# galvanika-board-2_2.net
KiCad netlist of a schematic drawn in EAGLE
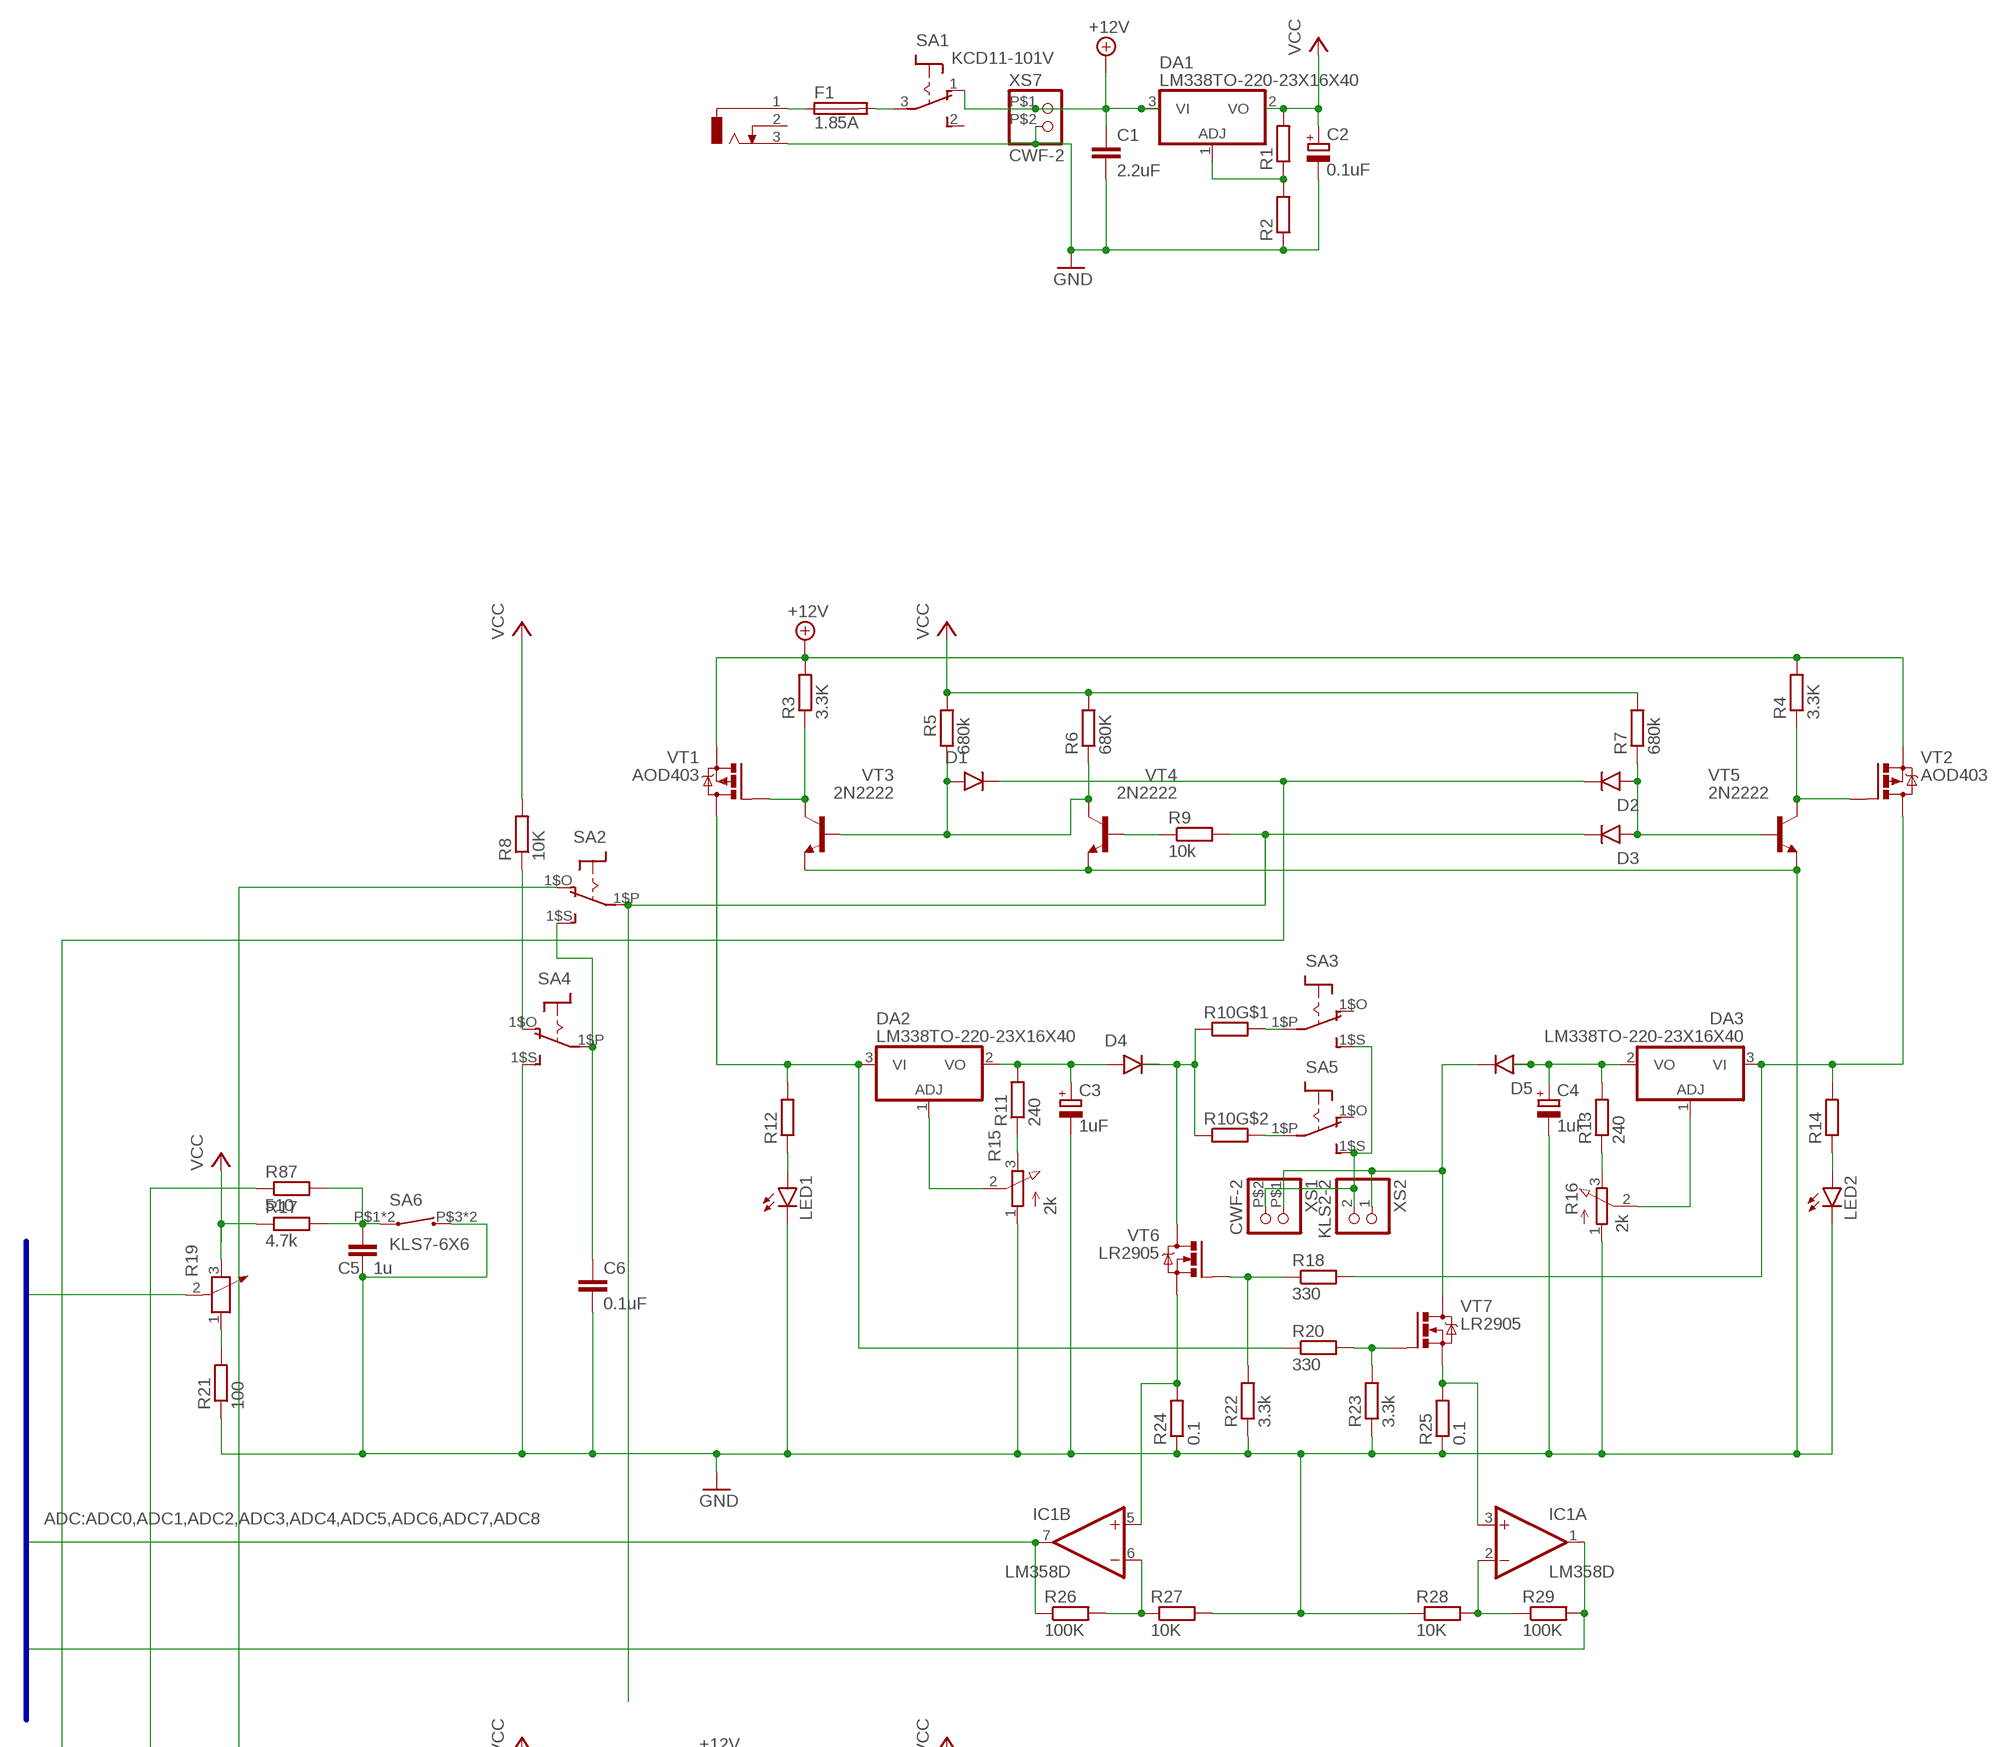
[diagram p0: schematic, sheet 1, part 1 of 2]
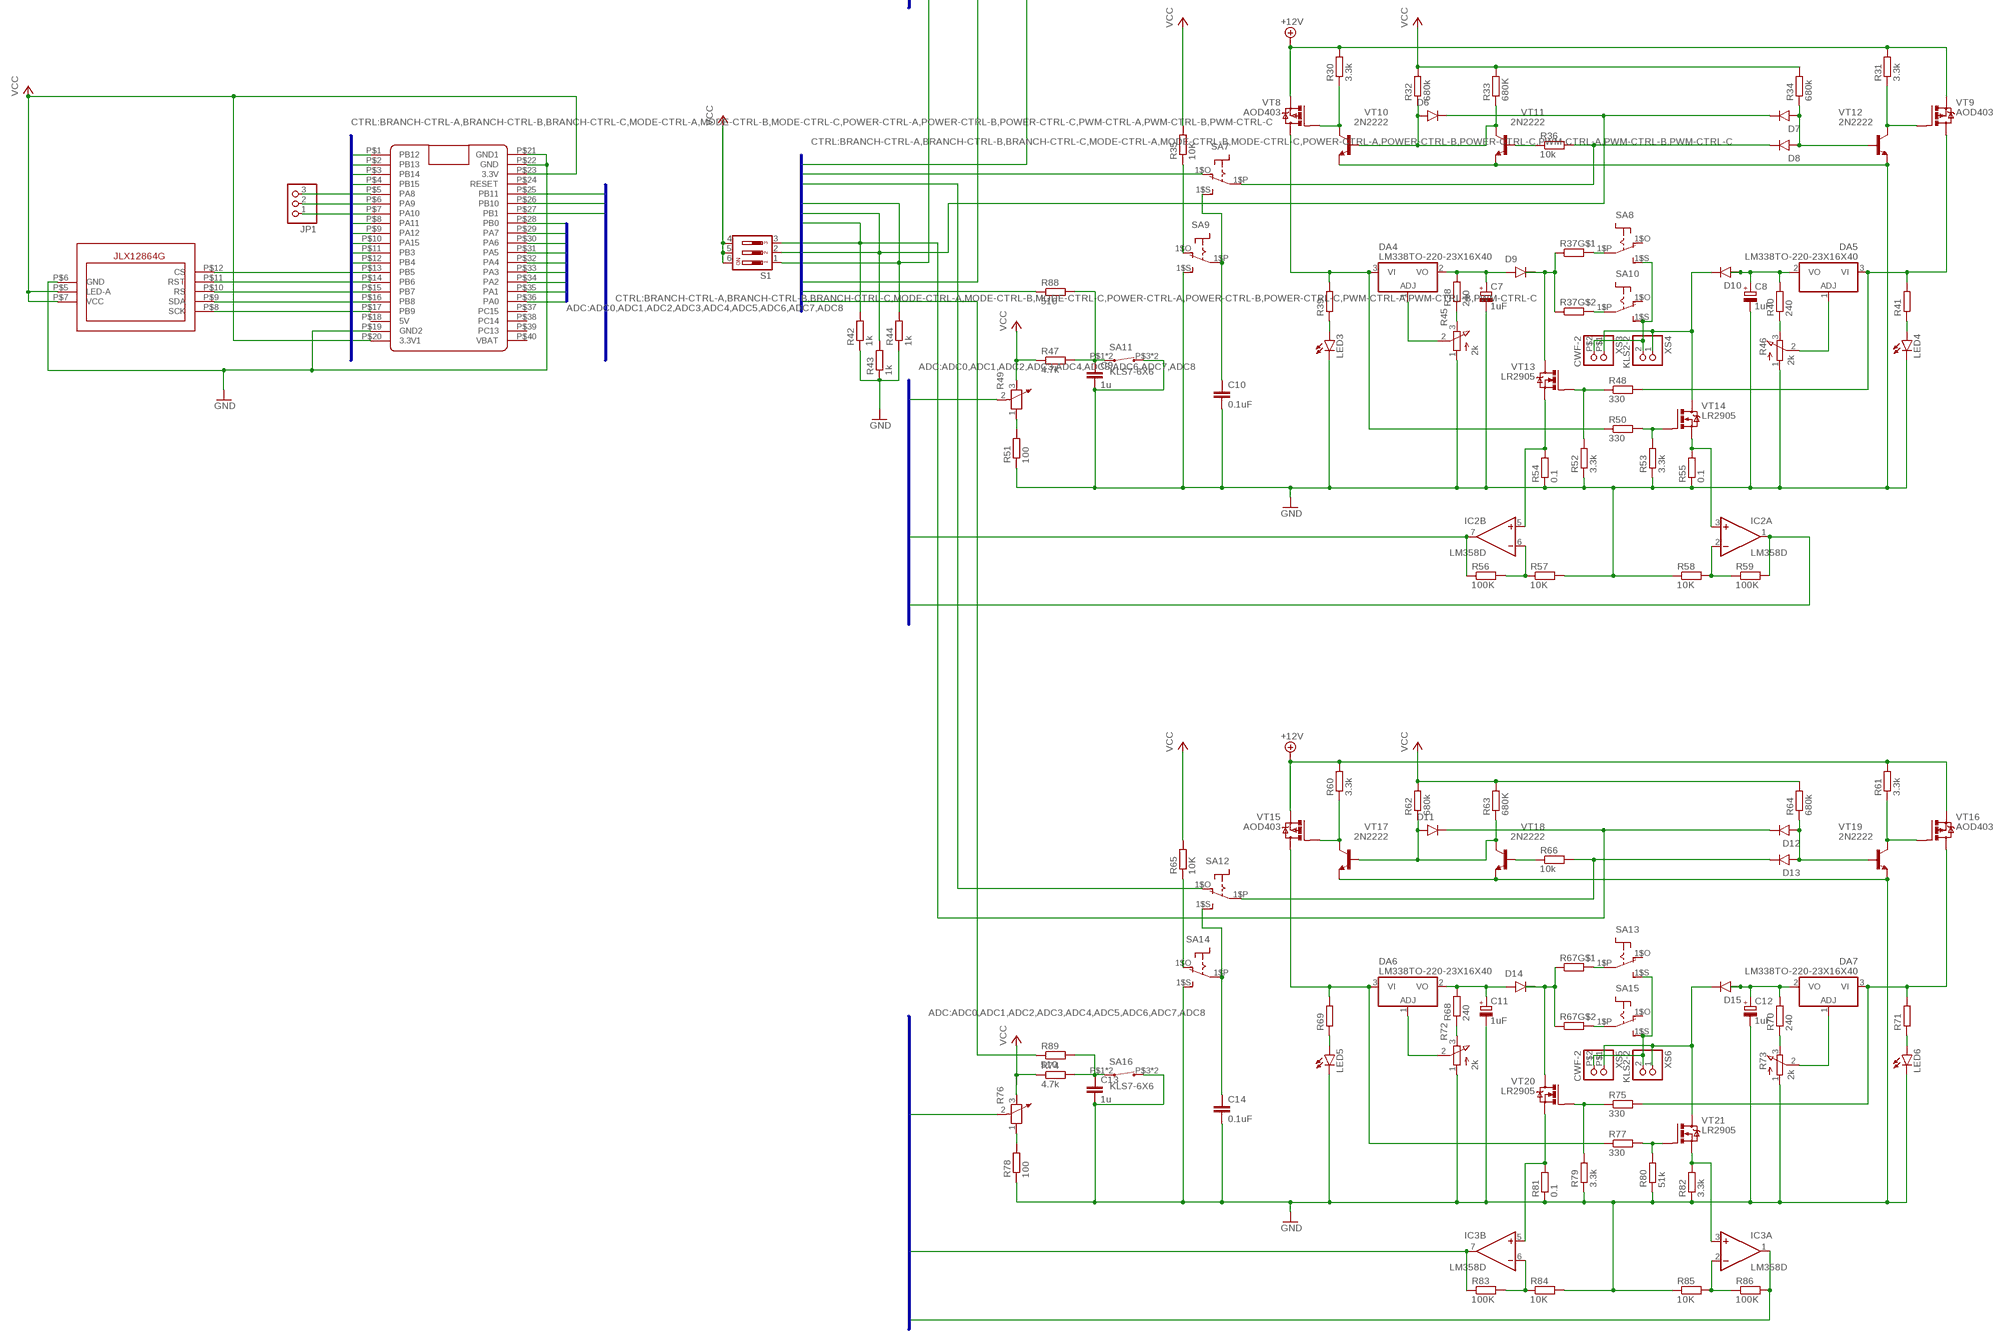
[diagram p1: schematic, sheet 1, part 2 of 2]

(export (version "E")
  (design (tool "Eeschema 10.0.6"))
  (components
    (comp (ref "C1")
      (value "2.2uF")
      (footprint "eagle-import:C025-025X050")
      (libsource (lib "eagle-import") (part "C-EU025-025X050"))
    )
    (comp (ref "C2")
      (value "0.1uF")
      (footprint "eagle-import:E2,5-5")
      (libsource (lib "eagle-import") (part "rcl_334_CPOL-EUE2.5-5"))
    )
    (comp (ref "C3")
      (value "1uF")
      (footprint "eagle-import:E5-4")
      (libsource (lib "eagle-import") (part "CPOL-EUE5-4"))
    )
    (comp (ref "C4")
      (value "1uF")
      (footprint "eagle-import:E5-4")
      (libsource (lib "eagle-import") (part "CPOL-EUE5-4"))
    )
    (comp (ref "C5")
      (value "1u")
      (footprint "eagle-import:C1206")
      (libsource (lib "eagle-import") (part "C-EUC1206"))
    )
    (comp (ref "C6")
      (value "0.1uF")
      (footprint "eagle-import:C1206")
      (libsource (lib "eagle-import") (part "C-EUC1206"))
    )
    (comp (ref "C7")
      (value "1uF")
      (footprint "eagle-import:E5-4")
      (libsource (lib "eagle-import") (part "CPOL-EUE5-4"))
    )
    (comp (ref "C8")
      (value "1uF")
      (footprint "eagle-import:E5-4")
      (libsource (lib "eagle-import") (part "CPOL-EUE5-4"))
    )
    (comp (ref "C9")
      (value "1u")
      (footprint "eagle-import:C1206")
      (libsource (lib "eagle-import") (part "C-EUC1206"))
    )
    (comp (ref "C10")
      (value "0.1uF")
      (footprint "eagle-import:C1206")
      (libsource (lib "eagle-import") (part "C-EUC1206"))
    )
    (comp (ref "C11")
      (value "1uF")
      (footprint "eagle-import:E5-4")
      (libsource (lib "eagle-import") (part "CPOL-EUE5-4"))
    )
    (comp (ref "C12")
      (value "1uF")
      (footprint "eagle-import:E5-4")
      (libsource (lib "eagle-import") (part "CPOL-EUE5-4"))
    )
    (comp (ref "C13")
      (value "1u")
      (footprint "eagle-import:C1206")
      (libsource (lib "eagle-import") (part "C-EUC1206"))
    )
    (comp (ref "C14")
      (value "0.1uF")
      (footprint "eagle-import:C1206")
      (libsource (lib "eagle-import") (part "C-EUC1206"))
    )
    (comp (ref "D1")
      (value "1N4001")
      (footprint "eagle-import:DO41-10")
      (libsource (lib "eagle-import") (part "1N4001"))
    )
    (comp (ref "D2")
      (value "1N4001")
      (footprint "eagle-import:DO41-10")
      (libsource (lib "eagle-import") (part "1N4001"))
    )
    (comp (ref "D3")
      (value "1N4001")
      (footprint "eagle-import:DO41-10")
      (libsource (lib "eagle-import") (part "1N4001"))
    )
    (comp (ref "D4")
      (value "1N4001")
      (footprint "eagle-import:DO41-10")
      (libsource (lib "eagle-import") (part "1N4001"))
    )
    (comp (ref "D5")
      (value "1N4001")
      (footprint "eagle-import:DO41-10")
      (libsource (lib "eagle-import") (part "1N4001"))
    )
    (comp (ref "D6")
      (value "1N4001")
      (footprint "eagle-import:DO41-10")
      (libsource (lib "eagle-import") (part "1N4001"))
    )
    (comp (ref "D7")
      (value "1N4001")
      (footprint "eagle-import:DO41-10")
      (libsource (lib "eagle-import") (part "1N4001"))
    )
    (comp (ref "D8")
      (value "1N4001")
      (footprint "eagle-import:DO41-10")
      (libsource (lib "eagle-import") (part "1N4001"))
    )
    (comp (ref "D9")
      (value "1N4001")
      (footprint "eagle-import:DO41-10")
      (libsource (lib "eagle-import") (part "1N4001"))
    )
    (comp (ref "D10")
      (value "1N4001")
      (footprint "eagle-import:DO41-10")
      (libsource (lib "eagle-import") (part "1N4001"))
    )
    (comp (ref "D11")
      (value "1N4001")
      (footprint "eagle-import:DO41-10")
      (libsource (lib "eagle-import") (part "1N4001"))
    )
    (comp (ref "D12")
      (value "1N4001")
      (footprint "eagle-import:DO41-10")
      (libsource (lib "eagle-import") (part "1N4001"))
    )
    (comp (ref "D13")
      (value "1N4001")
      (footprint "eagle-import:DO41-10")
      (libsource (lib "eagle-import") (part "1N4001"))
    )
    (comp (ref "D14")
      (value "1N4001")
      (footprint "eagle-import:DO41-10")
      (libsource (lib "eagle-import") (part "1N4001"))
    )
    (comp (ref "D15")
      (value "1N4001")
      (footprint "eagle-import:DO41-10")
      (libsource (lib "eagle-import") (part "1N4001"))
    )
    (comp (ref "DA1")
      (value "LM338TO-220-23X16X40")
      (footprint "eagle-import:TO220-23X16X40")
      (libsource (lib "eagle-import") (part "LM338TO-220-23X16X40"))
    )
    (comp (ref "DA2")
      (value "LM338TO-220-23X16X40")
      (footprint "eagle-import:TO220-23X16X40")
      (libsource (lib "eagle-import") (part "LM338TO-220-23X16X40"))
    )
    (comp (ref "DA3")
      (value "LM338TO-220-23X16X40")
      (footprint "eagle-import:TO220-23X16X40")
      (libsource (lib "eagle-import") (part "LM338TO-220-23X16X40"))
    )
    (comp (ref "DA4")
      (value "LM338TO-220-23X16X40")
      (footprint "eagle-import:TO220-23X16X40")
      (libsource (lib "eagle-import") (part "LM338TO-220-23X16X40"))
    )
    (comp (ref "DA5")
      (value "LM338TO-220-23X16X40")
      (footprint "eagle-import:TO220-23X16X40")
      (libsource (lib "eagle-import") (part "LM338TO-220-23X16X40"))
    )
    (comp (ref "DA6")
      (value "LM338TO-220-23X16X40")
      (footprint "eagle-import:TO220-23X16X40")
      (libsource (lib "eagle-import") (part "LM338TO-220-23X16X40"))
    )
    (comp (ref "DA7")
      (value "LM338TO-220-23X16X40")
      (footprint "eagle-import:TO220-23X16X40")
      (libsource (lib "eagle-import") (part "LM338TO-220-23X16X40"))
    )
    (comp (ref "DD1")
      (value "BLUE_PILL")
      (footprint "eagle-import:BLUE_PILL")
      (libsource (lib "eagle-import") (part "BLUE_PILL"))
    )
    (comp (ref "F1")
      (value "1.85A")
      (footprint "eagle-import:MF-R")
      (libsource (lib "eagle-import") (part "MF-R"))
    )
    (comp (ref "HG1")
      (value "JLX12864G")
      (footprint "eagle-import:JLX12864G")
      (libsource (lib "eagle-import") (part "JLX12864G"))
    )
    (comp (ref "IC1")
      (value "LM358D")
      (footprint "eagle-import:SO08")
      (libsource (lib "eagle-import") (part "LM358D"))
    )
    (comp (ref "IC2")
      (value "LM358D")
      (footprint "eagle-import:SO08")
      (libsource (lib "eagle-import") (part "LM358D"))
    )
    (comp (ref "IC3")
      (value "LM358D")
      (footprint "eagle-import:SO08")
      (libsource (lib "eagle-import") (part "LM358D"))
    )
    (comp (ref "J1")
      (value "DCJ0303")
      (footprint "eagle-import:DCJ0303")
      (libsource (lib "eagle-import") (part "DCJ0303"))
    )
    (comp (ref "JP1")
      (value "PINHD-1X3")
      (footprint "eagle-import:1X03")
      (libsource (lib "eagle-import") (part "PINHD-1X3"))
    )
    (comp (ref "LED1")
      (value "LED3MM")
      (footprint "eagle-import:LED3MM")
      (libsource (lib "eagle-import") (part "LED3MM"))
    )
    (comp (ref "LED2")
      (value "LED3MM")
      (footprint "eagle-import:LED3MM")
      (libsource (lib "eagle-import") (part "LED3MM"))
    )
    (comp (ref "LED3")
      (value "LED3MM")
      (footprint "eagle-import:LED3MM")
      (libsource (lib "eagle-import") (part "LED3MM"))
    )
    (comp (ref "LED4")
      (value "LED3MM")
      (footprint "eagle-import:LED3MM")
      (libsource (lib "eagle-import") (part "LED3MM"))
    )
    (comp (ref "LED5")
      (value "LED3MM")
      (footprint "eagle-import:LED3MM")
      (libsource (lib "eagle-import") (part "LED3MM"))
    )
    (comp (ref "LED6")
      (value "LED3MM")
      (footprint "eagle-import:LED3MM")
      (libsource (lib "eagle-import") (part "LED3MM"))
    )
    (comp (ref "R1")
      (value "R-EU_0207/10")
      (footprint "eagle-import:0207_10")
      (libsource (lib "eagle-import") (part "R-EU_0207/10"))
    )
    (comp (ref "R2")
      (value "R-EU_0207/10")
      (footprint "eagle-import:0207_10")
      (libsource (lib "eagle-import") (part "R-EU_0207/10"))
    )
    (comp (ref "R3")
      (value "3.3K")
      (footprint "eagle-import:0207_10")
      (libsource (lib "eagle-import") (part "rcl_334_R-EU_0207/10"))
    )
    (comp (ref "R4")
      (value "3.3K")
      (footprint "eagle-import:0207_10")
      (libsource (lib "eagle-import") (part "rcl_334_R-EU_0207/10"))
    )
    (comp (ref "R5")
      (value "680k")
      (footprint "eagle-import:0207_10")
      (libsource (lib "eagle-import") (part "rcl_334_R-EU_0207/10"))
    )
    (comp (ref "R6")
      (value "680K")
      (footprint "eagle-import:0207_10")
      (libsource (lib "eagle-import") (part "rcl_334_R-EU_0207/10"))
    )
    (comp (ref "R7")
      (value "680k")
      (footprint "eagle-import:0207_10")
      (libsource (lib "eagle-import") (part "rcl_334_R-EU_0207/10"))
    )
    (comp (ref "R8")
      (value "10K")
      (footprint "eagle-import:0207_10")
      (libsource (lib "eagle-import") (part "rcl_334_R-EU_0207/10"))
    )
    (comp (ref "R9")
      (value "10k")
      (footprint "eagle-import:0207_10")
      (libsource (lib "eagle-import") (part "rcl_334_R-EU_0207/10"))
    )
    (comp (ref "R10")
      (value "SQP-5W-2")
      (footprint "eagle-import:SQP-5W-2")
      (libsource (lib "eagle-import") (part "SQP-5W-2"))
    )
    (comp (ref "R11")
      (value "240")
      (footprint "eagle-import:0207_10")
      (libsource (lib "eagle-import") (part "rcl_334_R-EU_0207/10"))
    )
    (comp (ref "R12")
      (value "R-EU_0207/10")
      (footprint "eagle-import:0207_10")
      (libsource (lib "eagle-import") (part "rcl_334_R-EU_0207/10"))
    )
    (comp (ref "R13")
      (value "240")
      (footprint "eagle-import:0207_10")
      (libsource (lib "eagle-import") (part "rcl_334_R-EU_0207/10"))
    )
    (comp (ref "R14")
      (value "R-EU_0207/10")
      (footprint "eagle-import:0207_10")
      (libsource (lib "eagle-import") (part "rcl_334_R-EU_0207/10"))
    )
    (comp (ref "R15")
      (value "2k")
      (footprint "eagle-import:3RP_1610N")
      (libsource (lib "eagle-import") (part "3RP/1610N"))
    )
    (comp (ref "R16")
      (value "2k")
      (footprint "eagle-import:3RP_1610N")
      (libsource (lib "eagle-import") (part "3RP/1610N"))
    )
    (comp (ref "R17")
      (value "4.7k")
      (footprint "eagle-import:R1206")
      (libsource (lib "eagle-import") (part "R-EU_R1206"))
    )
    (comp (ref "R18")
      (value "330")
      (footprint "eagle-import:0207_10")
      (libsource (lib "eagle-import") (part "rcl_334_R-EU_0207/10"))
    )
    (comp (ref "R19")
      (value "R0904N")
      (footprint "eagle-import:R0904N")
      (libsource (lib "eagle-import") (part "R0904N"))
    )
    (comp (ref "R20")
      (value "330")
      (footprint "eagle-import:0207_10")
      (libsource (lib "eagle-import") (part "rcl_334_R-EU_0207/10"))
    )
    (comp (ref "R21")
      (value "100")
      (footprint "eagle-import:R1206")
      (libsource (lib "eagle-import") (part "R-EU_R1206"))
    )
    (comp (ref "R22")
      (value "3.3k")
      (footprint "eagle-import:0207_10")
      (libsource (lib "eagle-import") (part "rcl_334_R-EU_0207/10"))
    )
    (comp (ref "R23")
      (value "3.3k")
      (footprint "eagle-import:0207_10")
      (libsource (lib "eagle-import") (part "rcl_334_R-EU_0207/10"))
    )
    (comp (ref "R24")
      (value "0.1")
      (footprint "eagle-import:0411_12")
      (libsource (lib "eagle-import") (part "rcl_334_R-EU_0411/12"))
    )
    (comp (ref "R25")
      (value "0.1")
      (footprint "eagle-import:0411_12")
      (libsource (lib "eagle-import") (part "rcl_334_R-EU_0411/12"))
    )
    (comp (ref "R26")
      (value "100K")
      (footprint "eagle-import:R1206")
      (libsource (lib "eagle-import") (part "rcl_334_R-EU_R1206"))
    )
    (comp (ref "R27")
      (value "10K")
      (footprint "eagle-import:R1206")
      (libsource (lib "eagle-import") (part "rcl_334_R-EU_R1206"))
    )
    (comp (ref "R28")
      (value "10K")
      (footprint "eagle-import:R1206")
      (libsource (lib "eagle-import") (part "rcl_334_R-EU_R1206"))
    )
    (comp (ref "R29")
      (value "100K")
      (footprint "eagle-import:R1206")
      (libsource (lib "eagle-import") (part "rcl_334_R-EU_R1206"))
    )
    (comp (ref "R30")
      (value "3.3k")
      (footprint "eagle-import:0207_10")
      (libsource (lib "eagle-import") (part "rcl_334_R-EU_0207/10"))
    )
    (comp (ref "R31")
      (value "3.3k")
      (footprint "eagle-import:0207_10")
      (libsource (lib "eagle-import") (part "rcl_334_R-EU_0207/10"))
    )
    (comp (ref "R32")
      (value "680k")
      (footprint "eagle-import:0207_10")
      (libsource (lib "eagle-import") (part "rcl_334_R-EU_0207/10"))
    )
    (comp (ref "R33")
      (value "680K")
      (footprint "eagle-import:0207_10")
      (libsource (lib "eagle-import") (part "rcl_334_R-EU_0207/10"))
    )
    (comp (ref "R34")
      (value "680k")
      (footprint "eagle-import:0207_10")
      (libsource (lib "eagle-import") (part "rcl_334_R-EU_0207/10"))
    )
    (comp (ref "R35")
      (value "10K")
      (footprint "eagle-import:0207_10")
      (libsource (lib "eagle-import") (part "rcl_334_R-EU_0207/10"))
    )
    (comp (ref "R36")
      (value "10k")
      (footprint "eagle-import:0207_10")
      (libsource (lib "eagle-import") (part "rcl_334_R-EU_0207/10"))
    )
    (comp (ref "R37")
      (value "SQP-5W-2")
      (footprint "eagle-import:SQP-5W-2")
      (libsource (lib "eagle-import") (part "SQP-5W-2"))
    )
    (comp (ref "R38")
      (value "240")
      (footprint "eagle-import:0207_10")
      (libsource (lib "eagle-import") (part "R-EU_0207/10"))
    )
    (comp (ref "R39")
      (value "R-EU_0207/10")
      (footprint "eagle-import:0207_10")
      (libsource (lib "eagle-import") (part "R-EU_0207/10"))
    )
    (comp (ref "R40")
      (value "240")
      (footprint "eagle-import:0207_10")
      (libsource (lib "eagle-import") (part "rcl_334_R-EU_0207/10"))
    )
    (comp (ref "R41")
      (value "R-EU_0207/10")
      (footprint "eagle-import:0207_10")
      (libsource (lib "eagle-import") (part "R-EU_0207/10"))
    )
    (comp (ref "R42")
      (value "1k")
      (footprint "eagle-import:R1206")
      (libsource (lib "eagle-import") (part "R-EU_R1206"))
    )
    (comp (ref "R43")
      (value "1k")
      (footprint "eagle-import:R1206")
      (libsource (lib "eagle-import") (part "R-EU_R1206"))
    )
    (comp (ref "R44")
      (value "1k")
      (footprint "eagle-import:R1206")
      (libsource (lib "eagle-import") (part "R-EU_R1206"))
    )
    (comp (ref "R45")
      (value "2k")
      (footprint "eagle-import:3RP_1610N")
      (libsource (lib "eagle-import") (part "3RP/1610N"))
    )
    (comp (ref "R46")
      (value "2k")
      (footprint "eagle-import:3RP_1610N")
      (libsource (lib "eagle-import") (part "3RP/1610N"))
    )
    (comp (ref "R47")
      (value "4.7k")
      (footprint "eagle-import:R1206")
      (libsource (lib "eagle-import") (part "R-EU_R1206"))
    )
    (comp (ref "R48")
      (value "330")
      (footprint "eagle-import:0207_10")
      (libsource (lib "eagle-import") (part "rcl_334_R-EU_0207/10"))
    )
    (comp (ref "R49")
      (value "R0904N")
      (footprint "eagle-import:R0904N")
      (libsource (lib "eagle-import") (part "R0904N"))
    )
    (comp (ref "R50")
      (value "330")
      (footprint "eagle-import:0207_10")
      (libsource (lib "eagle-import") (part "rcl_334_R-EU_0207/10"))
    )
    (comp (ref "R51")
      (value "100")
      (footprint "eagle-import:R1206")
      (libsource (lib "eagle-import") (part "R-EU_R1206"))
    )
    (comp (ref "R52")
      (value "3.3k")
      (footprint "eagle-import:0207_10")
      (libsource (lib "eagle-import") (part "rcl_334_R-EU_0207/10"))
    )
    (comp (ref "R53")
      (value "3.3k")
      (footprint "eagle-import:0207_10")
      (libsource (lib "eagle-import") (part "rcl_334_R-EU_0207/10"))
    )
    (comp (ref "R54")
      (value "0.1")
      (footprint "eagle-import:0411_12")
      (libsource (lib "eagle-import") (part "rcl_334_R-EU_0411/12"))
    )
    (comp (ref "R55")
      (value "0.1")
      (footprint "eagle-import:0411_12")
      (libsource (lib "eagle-import") (part "rcl_334_R-EU_0411/12"))
    )
    (comp (ref "R56")
      (value "100K")
      (footprint "eagle-import:R1206")
      (libsource (lib "eagle-import") (part "rcl_334_R-EU_R1206"))
    )
    (comp (ref "R57")
      (value "10K")
      (footprint "eagle-import:R1206")
      (libsource (lib "eagle-import") (part "rcl_334_R-EU_R1206"))
    )
    (comp (ref "R58")
      (value "10K")
      (footprint "eagle-import:R1206")
      (libsource (lib "eagle-import") (part "rcl_334_R-EU_R1206"))
    )
    (comp (ref "R59")
      (value "100K")
      (footprint "eagle-import:R1206")
      (libsource (lib "eagle-import") (part "rcl_334_R-EU_R1206"))
    )
    (comp (ref "R60")
      (value "3.3k")
      (footprint "eagle-import:0207_10")
      (libsource (lib "eagle-import") (part "rcl_334_R-EU_0207/10"))
    )
    (comp (ref "R61")
      (value "3.3k")
      (footprint "eagle-import:0207_10")
      (libsource (lib "eagle-import") (part "rcl_334_R-EU_0207/10"))
    )
    (comp (ref "R62")
      (value "680k")
      (footprint "eagle-import:0207_10")
      (libsource (lib "eagle-import") (part "rcl_334_R-EU_0207/10"))
    )
    (comp (ref "R63")
      (value "680K")
      (footprint "eagle-import:0207_10")
      (libsource (lib "eagle-import") (part "rcl_334_R-EU_0207/10"))
    )
    (comp (ref "R64")
      (value "680k")
      (footprint "eagle-import:0207_10")
      (libsource (lib "eagle-import") (part "rcl_334_R-EU_0207/10"))
    )
    (comp (ref "R65")
      (value "10K")
      (footprint "eagle-import:0207_10")
      (libsource (lib "eagle-import") (part "rcl_334_R-EU_0207/10"))
    )
    (comp (ref "R66")
      (value "10k")
      (footprint "eagle-import:0207_10")
      (libsource (lib "eagle-import") (part "rcl_334_R-EU_0207/10"))
    )
    (comp (ref "R67")
      (value "SQP-5W-2")
      (footprint "eagle-import:SQP-5W-2")
      (libsource (lib "eagle-import") (part "SQP-5W-2"))
    )
    (comp (ref "R68")
      (value "240")
      (footprint "eagle-import:0207_10")
      (libsource (lib "eagle-import") (part "rcl_334_R-EU_0207/10"))
    )
    (comp (ref "R69")
      (value "R-EU_0207/10")
      (footprint "eagle-import:0207_10")
      (libsource (lib "eagle-import") (part "rcl_334_R-EU_0207/10"))
    )
    (comp (ref "R70")
      (value "240")
      (footprint "eagle-import:0207_10")
      (libsource (lib "eagle-import") (part "rcl_334_R-EU_0207/10"))
    )
    (comp (ref "R71")
      (value "R-EU_0207/10")
      (footprint "eagle-import:0207_10")
      (libsource (lib "eagle-import") (part "rcl_334_R-EU_0207/10"))
    )
    (comp (ref "R72")
      (value "2k")
      (footprint "eagle-import:3RP_1610N")
      (libsource (lib "eagle-import") (part "3RP/1610N"))
    )
    (comp (ref "R73")
      (value "2k")
      (footprint "eagle-import:3RP_1610N")
      (libsource (lib "eagle-import") (part "3RP/1610N"))
    )
    (comp (ref "R74")
      (value "4.7k")
      (footprint "eagle-import:R1206")
      (libsource (lib "eagle-import") (part "R-EU_R1206"))
    )
    (comp (ref "R75")
      (value "330")
      (footprint "eagle-import:0207_10")
      (libsource (lib "eagle-import") (part "rcl_334_R-EU_0207/10"))
    )
    (comp (ref "R76")
      (value "R0904N")
      (footprint "eagle-import:R0904N")
      (libsource (lib "eagle-import") (part "R0904N"))
    )
    (comp (ref "R77")
      (value "330")
      (footprint "eagle-import:0207_10")
      (libsource (lib "eagle-import") (part "rcl_334_R-EU_0207/10"))
    )
    (comp (ref "R78")
      (value "100")
      (footprint "eagle-import:R1206")
      (libsource (lib "eagle-import") (part "R-EU_R1206"))
    )
    (comp (ref "R79")
      (value "3.3k")
      (footprint "eagle-import:0207_10")
      (libsource (lib "eagle-import") (part "rcl_334_R-EU_0207/10"))
    )
    (comp (ref "R80")
      (value "51k")
      (footprint "eagle-import:0207_10")
      (libsource (lib "eagle-import") (part "rcl_334_R-EU_0207/10"))
    )
    (comp (ref "R81")
      (value "0.1")
      (footprint "eagle-import:0411_12")
      (libsource (lib "eagle-import") (part "rcl_334_R-EU_0411/12"))
    )
    (comp (ref "R82")
      (value "3.3k")
      (footprint "eagle-import:0411_12")
      (libsource (lib "eagle-import") (part "rcl_334_R-EU_0411/12"))
    )
    (comp (ref "R83")
      (value "100K")
      (footprint "eagle-import:R1206")
      (libsource (lib "eagle-import") (part "rcl_334_R-EU_R1206"))
    )
    (comp (ref "R84")
      (value "10K")
      (footprint "eagle-import:R1206")
      (libsource (lib "eagle-import") (part "rcl_334_R-EU_R1206"))
    )
    (comp (ref "R85")
      (value "10K")
      (footprint "eagle-import:R1206")
      (libsource (lib "eagle-import") (part "rcl_334_R-EU_R1206"))
    )
    (comp (ref "R86")
      (value "100K")
      (footprint "eagle-import:R1206")
      (libsource (lib "eagle-import") (part "rcl_334_R-EU_R1206"))
    )
    (comp (ref "R87")
      (value "510")
      (footprint "eagle-import:R1206")
      (libsource (lib "eagle-import") (part "R-EU_R1206"))
    )
    (comp (ref "R88")
      (value "510")
      (footprint "eagle-import:R1206")
      (libsource (lib "eagle-import") (part "R-EU_R1206"))
    )
    (comp (ref "R89")
      (value "510")
      (footprint "eagle-import:R1206")
      (libsource (lib "eagle-import") (part "R-EU_R1206"))
    )
    (comp (ref "S1")
      (value "DS03")
      (footprint "eagle-import:DS-03")
      (libsource (lib "eagle-import") (part "DS03"))
    )
    (comp (ref "SA1")
      (value "KCD11-101V")
      (footprint "eagle-import:KCD11-101-V")
      (libsource (lib "eagle-import") (part "KCD11-101V"))
    )
    (comp (ref "SA2")
      (value "SS12D00DIP")
      (footprint "eagle-import:SS12D00")
      (libsource (lib "eagle-import") (part "SS12D00DIP"))
    )
    (comp (ref "SA3")
      (value "SS12D00DIP")
      (footprint "eagle-import:SS12D00")
      (libsource (lib "eagle-import") (part "SS12D00DIP"))
    )
    (comp (ref "SA4")
      (value "SS12D00DIP")
      (footprint "eagle-import:SS12D00")
      (libsource (lib "eagle-import") (part "SS12D00DIP"))
    )
    (comp (ref "SA5")
      (value "SS12D00DIP")
      (footprint "eagle-import:SS12D00")
      (libsource (lib "eagle-import") (part "SS12D00DIP"))
    )
    (comp (ref "SA6")
      (value "KLS7-6X6")
      (footprint "eagle-import:KLS7-6X6")
      (libsource (lib "eagle-import") (part "KLS7-6X6"))
    )
    (comp (ref "SA7")
      (value "SS12D00DIP")
      (footprint "eagle-import:SS12D00")
      (libsource (lib "eagle-import") (part "SS12D00DIP"))
    )
    (comp (ref "SA8")
      (value "SS12D00DIP")
      (footprint "eagle-import:SS12D00")
      (libsource (lib "eagle-import") (part "SS12D00DIP"))
    )
    (comp (ref "SA9")
      (value "SS12D00DIP")
      (footprint "eagle-import:SS12D00")
      (libsource (lib "eagle-import") (part "SS12D00DIP"))
    )
    (comp (ref "SA10")
      (value "SS12D00DIP")
      (footprint "eagle-import:SS12D00")
      (libsource (lib "eagle-import") (part "SS12D00DIP"))
    )
    (comp (ref "SA11")
      (value "KLS7-6X6")
      (footprint "eagle-import:KLS7-6X6")
      (libsource (lib "eagle-import") (part "KLS7-6X6"))
    )
    (comp (ref "SA12")
      (value "SS12D00DIP")
      (footprint "eagle-import:SS12D00")
      (libsource (lib "eagle-import") (part "SS12D00DIP"))
    )
    (comp (ref "SA13")
      (value "SS12D00DIP")
      (footprint "eagle-import:SS12D00")
      (libsource (lib "eagle-import") (part "SS12D00DIP"))
    )
    (comp (ref "SA14")
      (value "SS12D00DIP")
      (footprint "eagle-import:SS12D00")
      (libsource (lib "eagle-import") (part "SS12D00DIP"))
    )
    (comp (ref "SA15")
      (value "SS12D00DIP")
      (footprint "eagle-import:SS12D00")
      (libsource (lib "eagle-import") (part "SS12D00DIP"))
    )
    (comp (ref "SA16")
      (value "KLS7-6X6")
      (footprint "eagle-import:KLS7-6X6")
      (libsource (lib "eagle-import") (part "KLS7-6X6"))
    )
    (comp (ref "VT1")
      (value "AOD403")
      (footprint "eagle-import:TO252")
      (libsource (lib "eagle-import") (part "AOD403"))
    )
    (comp (ref "VT2")
      (value "AOD403")
      (footprint "eagle-import:TO252")
      (libsource (lib "eagle-import") (part "AOD403"))
    )
    (comp (ref "VT3")
      (value "2N2222")
      (footprint "eagle-import:TO92")
      (libsource (lib "eagle-import") (part "2N2222"))
    )
    (comp (ref "VT4")
      (value "2N2222")
      (footprint "eagle-import:TO92")
      (libsource (lib "eagle-import") (part "2N2222"))
    )
    (comp (ref "VT5")
      (value "2N2222")
      (footprint "eagle-import:TO92")
      (libsource (lib "eagle-import") (part "2N2222"))
    )
    (comp (ref "VT6")
      (value "LR2905")
      (footprint "eagle-import:TO252")
      (libsource (lib "eagle-import") (part "LR2905"))
    )
    (comp (ref "VT7")
      (value "LR2905")
      (footprint "eagle-import:TO252")
      (libsource (lib "eagle-import") (part "LR2905"))
    )
    (comp (ref "VT8")
      (value "AOD403")
      (footprint "eagle-import:TO252")
      (libsource (lib "eagle-import") (part "AOD403"))
    )
    (comp (ref "VT9")
      (value "AOD403")
      (footprint "eagle-import:TO252")
      (libsource (lib "eagle-import") (part "AOD403"))
    )
    (comp (ref "VT10")
      (value "2N2222")
      (footprint "eagle-import:TO92")
      (libsource (lib "eagle-import") (part "2N2222"))
    )
    (comp (ref "VT11")
      (value "2N2222")
      (footprint "eagle-import:TO92")
      (libsource (lib "eagle-import") (part "2N2222"))
    )
    (comp (ref "VT12")
      (value "2N2222")
      (footprint "eagle-import:TO92")
      (libsource (lib "eagle-import") (part "2N2222"))
    )
    (comp (ref "VT13")
      (value "LR2905")
      (footprint "eagle-import:TO252")
      (libsource (lib "eagle-import") (part "LR2905"))
    )
    (comp (ref "VT14")
      (value "LR2905")
      (footprint "eagle-import:TO252")
      (libsource (lib "eagle-import") (part "LR2905"))
    )
    (comp (ref "VT15")
      (value "AOD403")
      (footprint "eagle-import:TO252")
      (libsource (lib "eagle-import") (part "AOD403"))
    )
    (comp (ref "VT16")
      (value "AOD403")
      (footprint "eagle-import:TO252")
      (libsource (lib "eagle-import") (part "AOD403"))
    )
    (comp (ref "VT17")
      (value "2N2222")
      (footprint "eagle-import:TO92")
      (libsource (lib "eagle-import") (part "2N2222"))
    )
    (comp (ref "VT18")
      (value "2N2222")
      (footprint "eagle-import:TO92")
      (libsource (lib "eagle-import") (part "2N2222"))
    )
    (comp (ref "VT19")
      (value "2N2222")
      (footprint "eagle-import:TO92")
      (libsource (lib "eagle-import") (part "2N2222"))
    )
    (comp (ref "VT20")
      (value "LR2905")
      (footprint "eagle-import:TO252")
      (libsource (lib "eagle-import") (part "LR2905"))
    )
    (comp (ref "VT21")
      (value "LR2905")
      (footprint "eagle-import:TO252")
      (libsource (lib "eagle-import") (part "LR2905"))
    )
    (comp (ref "XS1")
      (value "CWF-2")
      (footprint "eagle-import:CWF-2")
      (libsource (lib "eagle-import") (part "CWF-2"))
    )
    (comp (ref "XS2")
      (value "KLS2-2")
      (footprint "eagle-import:KLS2-2")
      (libsource (lib "eagle-import") (part "KLS2-2"))
    )
    (comp (ref "XS3")
      (value "CWF-2")
      (footprint "eagle-import:CWF-2")
      (libsource (lib "eagle-import") (part "CWF-2"))
    )
    (comp (ref "XS4")
      (value "KLS2-2")
      (footprint "eagle-import:KLS2-2")
      (libsource (lib "eagle-import") (part "KLS2-2"))
    )
    (comp (ref "XS5")
      (value "CWF-2")
      (footprint "eagle-import:CWF-2")
      (libsource (lib "eagle-import") (part "CWF-2"))
    )
    (comp (ref "XS6")
      (value "KLS2-2")
      (footprint "eagle-import:KLS2-2")
      (libsource (lib "eagle-import") (part "KLS2-2"))
    )
    (comp (ref "XS7")
      (value "CWF-2")
      (footprint "eagle-import:CWF-2")
      (libsource (lib "eagle-import") (part "CWF-2"))
    )
  )
  (nets
    (net (code "3") (name "+12V") (class "Default")
      (node (ref "C1") (pin "1") (pinfunction "1_1") (pintype "passive"))
      (node (ref "DA1") (pin "3") (pinfunction "VI_3") (pintype "input"))
      (node (ref "R3") (pin "2") (pinfunction "2_2") (pintype "passive"))
      (node (ref "R30") (pin "2") (pinfunction "2_2") (pintype "passive"))
      (node (ref "R31") (pin "2") (pinfunction "2_2") (pintype "passive"))
      (node (ref "R4") (pin "2") (pinfunction "2_2") (pintype "passive"))
      (node (ref "R60") (pin "2") (pinfunction "2_2") (pintype "passive"))
      (node (ref "R61") (pin "2") (pinfunction "2_2") (pintype "passive"))
      (node (ref "SA1") (pin "1") (pinfunction "O_1") (pintype "passive"))
      (node (ref "VT1") (pin "2") (pinfunction "S_2") (pintype "passive"))
      (node (ref "VT15") (pin "2") (pinfunction "S_2") (pintype "passive"))
      (node (ref "VT16") (pin "2") (pinfunction "S_2") (pintype "passive"))
      (node (ref "VT2") (pin "2") (pinfunction "S_2") (pintype "passive"))
      (node (ref "VT8") (pin "2") (pinfunction "S_2") (pintype "passive"))
      (node (ref "VT9") (pin "2") (pinfunction "S_2") (pintype "passive"))
      (node (ref "XS7") (pin "P$1") (pinfunction "1_P$1") (pintype "passive"))
    )
    (net (code "4") (name "/ADC0") (class "Default")
      (node (ref "DD1") (pin "P$36") (pinfunction "PA0_P$36") (pintype "bidirectional"))
      (node (ref "R19") (pin "2") (pinfunction "3_2") (pintype "passive"))
    )
    (net (code "5") (name "/ADC1") (class "Default")
      (node (ref "DD1") (pin "P$35") (pinfunction "PA1_P$35") (pintype "bidirectional"))
      (node (ref "R49") (pin "2") (pinfunction "3_2") (pintype "passive"))
    )
    (net (code "6") (name "/ADC2") (class "Default")
      (node (ref "DD1") (pin "P$34") (pinfunction "PA2_P$34") (pintype "bidirectional"))
      (node (ref "IC1") (pin "7") (pinfunction "OUT_7") (pintype "output"))
      (node (ref "R26") (pin "1") (pinfunction "1_1") (pintype "passive"))
    )
    (net (code "7") (name "/ADC3") (class "Default")
      (node (ref "DD1") (pin "P$33") (pinfunction "PA3_P$33") (pintype "bidirectional"))
      (node (ref "IC1") (pin "1") (pinfunction "OUT_1") (pintype "output"))
      (node (ref "R29") (pin "2") (pinfunction "2_2") (pintype "passive"))
    )
    (net (code "8") (name "/ADC4") (class "Default")
      (node (ref "DD1") (pin "P$32") (pinfunction "PA4_P$32") (pintype "bidirectional"))
      (node (ref "R76") (pin "2") (pinfunction "3_2") (pintype "passive"))
    )
    (net (code "9") (name "/ADC5") (class "Default")
      (node (ref "DD1") (pin "P$31") (pinfunction "PA5_P$31") (pintype "bidirectional"))
      (node (ref "IC2") (pin "1") (pinfunction "OUT_1") (pintype "output"))
      (node (ref "R59") (pin "2") (pinfunction "2_2") (pintype "passive"))
    )
    (net (code "10") (name "/ADC6") (class "Default")
      (node (ref "DD1") (pin "P$30") (pinfunction "PA6_P$30") (pintype "bidirectional"))
      (node (ref "IC2") (pin "7") (pinfunction "OUT_7") (pintype "output"))
      (node (ref "R56") (pin "1") (pinfunction "1_1") (pintype "passive"))
    )
    (net (code "11") (name "/ADC7") (class "Default")
      (node (ref "DD1") (pin "P$29") (pinfunction "PA7_P$29") (pintype "bidirectional"))
      (node (ref "IC3") (pin "7") (pinfunction "OUT_7") (pintype "output"))
      (node (ref "R83") (pin "1") (pinfunction "1_1") (pintype "passive"))
    )
    (net (code "12") (name "/ADC8") (class "Default")
      (node (ref "DD1") (pin "P$28") (pinfunction "PB0_P$28") (pintype "bidirectional"))
      (node (ref "IC3") (pin "1") (pinfunction "OUT_1") (pintype "output"))
      (node (ref "R86") (pin "2") (pinfunction "2_2") (pintype "passive"))
    )
    (net (code "13") (name "/BRANCH-CTRL-A") (class "Default")
      (node (ref "D3") (pin "C") (pinfunction "CATHODE_C") (pintype "passive"))
      (node (ref "DD1") (pin "P$9") (pinfunction "PA12_P$9") (pintype "bidirectional"))
      (node (ref "R9") (pin "2") (pinfunction "2_2") (pintype "passive"))
      (node (ref "SA2") (pin "1$P") (pinfunction "P_1$P") (pintype "passive"))
    )
    (net (code "14") (name "/BRANCH-CTRL-B") (class "Default")
      (node (ref "D8") (pin "C") (pinfunction "CATHODE_C") (pintype "passive"))
      (node (ref "DD1") (pin "P$8") (pinfunction "PA11_P$8") (pintype "bidirectional"))
      (node (ref "R36") (pin "2") (pinfunction "2_2") (pintype "passive"))
      (node (ref "SA7") (pin "1$P") (pinfunction "P_1$P") (pintype "passive"))
    )
    (net (code "15") (name "/BRANCH-CTRL-C") (class "Default")
      (node (ref "D13") (pin "C") (pinfunction "CATHODE_C") (pintype "passive"))
      (node (ref "DD1") (pin "P$4") (pinfunction "PB15_P$4") (pintype "bidirectional"))
      (node (ref "R66") (pin "2") (pinfunction "2_2") (pintype "passive"))
      (node (ref "SA12") (pin "1$P") (pinfunction "P_1$P") (pintype "passive"))
    )
    (net (code "16") (name "/MODE-CTRL-A") (class "Default")
      (node (ref "DD1") (pin "P$12") (pinfunction "PB4_P$12") (pintype "bidirectional"))
      (node (ref "R87") (pin "1") (pinfunction "1_1") (pintype "passive"))
    )
    (net (code "17") (name "/MODE-CTRL-B") (class "Default")
      (node (ref "DD1") (pin "P$11") (pinfunction "PB3_P$11") (pintype "bidirectional"))
      (node (ref "R88") (pin "1") (pinfunction "1_1") (pintype "passive"))
    )
    (net (code "18") (name "/MODE-CTRL-C") (class "Default")
      (node (ref "DD1") (pin "P$10") (pinfunction "PA15_P$10") (pintype "bidirectional"))
      (node (ref "R89") (pin "1") (pinfunction "1_1") (pintype "passive"))
    )
    (net (code "19") (name "/POWER-CTRL-A") (class "Default")
      (node (ref "D1") (pin "C") (pinfunction "CATHODE_C") (pintype "passive"))
      (node (ref "D2") (pin "C") (pinfunction "CATHODE_C") (pintype "passive"))
      (node (ref "DD1") (pin "P$27") (pinfunction "PB1_P$27") (pintype "bidirectional"))
      (node (ref "R44") (pin "2") (pinfunction "2_2") (pintype "passive"))
      (node (ref "S1") (pin "1") (pinfunction "1_1") (pintype "passive"))
    )
    (net (code "20") (name "/POWER-CTRL-B") (class "Default")
      (node (ref "D6") (pin "C") (pinfunction "CATHODE_C") (pintype "passive"))
      (node (ref "D7") (pin "C") (pinfunction "CATHODE_C") (pintype "passive"))
      (node (ref "DD1") (pin "P$26") (pinfunction "PB10_P$26") (pintype "bidirectional"))
      (node (ref "R43") (pin "2") (pinfunction "2_2") (pintype "passive"))
      (node (ref "S1") (pin "2") (pinfunction "2_2") (pintype "passive"))
    )
    (net (code "21") (name "/POWER-CTRL-C") (class "Default")
      (node (ref "D11") (pin "C") (pinfunction "CATHODE_C") (pintype "passive"))
      (node (ref "D12") (pin "C") (pinfunction "CATHODE_C") (pintype "passive"))
      (node (ref "DD1") (pin "P$25") (pinfunction "PB11_P$25") (pintype "bidirectional"))
      (node (ref "R42") (pin "2") (pinfunction "2_2") (pintype "passive"))
      (node (ref "S1") (pin "3") (pinfunction "3_3") (pintype "passive"))
    )
    (net (code "22") (name "/PWM-CTRL-A") (class "Default")
      (node (ref "DD1") (pin "P$2") (pinfunction "PB13_P$2") (pintype "bidirectional"))
      (node (ref "SA2") (pin "1$O") (pinfunction "O_1$O") (pintype "passive"))
    )
    (net (code "23") (name "/PWM-CTRL-B") (class "Default")
      (node (ref "DD1") (pin "P$3") (pinfunction "PB14_P$3") (pintype "bidirectional"))
      (node (ref "SA7") (pin "1$O") (pinfunction "O_1$O") (pintype "passive"))
    )
    (net (code "24") (name "/PWM-CTRL-C") (class "Default")
      (node (ref "DD1") (pin "P$1") (pinfunction "PB12_P$1") (pintype "bidirectional"))
      (node (ref "SA12") (pin "1$O") (pinfunction "O_1$O") (pintype "passive"))
    )
    (net (code "27") (name "GND") (class "Default")
      (node (ref "C1") (pin "2") (pinfunction "2_2") (pintype "passive"))
      (node (ref "C10") (pin "2") (pinfunction "2_2") (pintype "passive"))
      (node (ref "C11") (pin "-") (pinfunction "-_-") (pintype "passive"))
      (node (ref "C12") (pin "-") (pinfunction "-_-") (pintype "passive"))
      (node (ref "C13") (pin "2") (pinfunction "2_2") (pintype "passive"))
      (node (ref "C14") (pin "2") (pinfunction "2_2") (pintype "passive"))
      (node (ref "C2") (pin "-") (pinfunction "-_-") (pintype "passive"))
      (node (ref "C3") (pin "-") (pinfunction "-_-") (pintype "passive"))
      (node (ref "C4") (pin "-") (pinfunction "-_-") (pintype "passive"))
      (node (ref "C5") (pin "2") (pinfunction "2_2") (pintype "passive"))
      (node (ref "C6") (pin "2") (pinfunction "2_2") (pintype "passive"))
      (node (ref "C7") (pin "-") (pinfunction "-_-") (pintype "passive"))
      (node (ref "C8") (pin "-") (pinfunction "-_-") (pintype "passive"))
      (node (ref "C9") (pin "2") (pinfunction "2_2") (pintype "passive"))
      (node (ref "DD1") (pin "P$19") (pinfunction "GND2_P$19") (pintype "bidirectional"))
      (node (ref "DD1") (pin "P$21") (pinfunction "GND1_P$21") (pintype "power_in"))
      (node (ref "DD1") (pin "P$22") (pinfunction "GND_P$22") (pintype "bidirectional"))
      (node (ref "HG1") (pin "P$6") (pinfunction "GND_P$6") (pintype "bidirectional"))
      (node (ref "J1") (pin "3") (pinfunction "3_3") (pintype "passive"))
      (node (ref "LED1") (pin "K") (pinfunction "C_K") (pintype "passive"))
      (node (ref "LED2") (pin "K") (pinfunction "C_K") (pintype "passive"))
      (node (ref "LED3") (pin "K") (pinfunction "C_K") (pintype "passive"))
      (node (ref "LED4") (pin "K") (pinfunction "C_K") (pintype "passive"))
      (node (ref "LED5") (pin "K") (pinfunction "C_K") (pintype "passive"))
      (node (ref "LED6") (pin "K") (pinfunction "C_K") (pintype "passive"))
      (node (ref "R15") (pin "1") (pinfunction "A_1") (pintype "passive"))
      (node (ref "R16") (pin "1") (pinfunction "A_1") (pintype "passive"))
      (node (ref "R2") (pin "1") (pinfunction "1_1") (pintype "passive"))
      (node (ref "R21") (pin "1") (pinfunction "1_1") (pintype "passive"))
      (node (ref "R22") (pin "1") (pinfunction "1_1") (pintype "passive"))
      (node (ref "R23") (pin "1") (pinfunction "1_1") (pintype "passive"))
      (node (ref "R24") (pin "1") (pinfunction "1_1") (pintype "passive"))
      (node (ref "R25") (pin "1") (pinfunction "1_1") (pintype "passive"))
      (node (ref "R27") (pin "2") (pinfunction "2_2") (pintype "passive"))
      (node (ref "R28") (pin "1") (pinfunction "1_1") (pintype "passive"))
      (node (ref "R42") (pin "1") (pinfunction "1_1") (pintype "passive"))
      (node (ref "R43") (pin "1") (pinfunction "1_1") (pintype "passive"))
      (node (ref "R44") (pin "1") (pinfunction "1_1") (pintype "passive"))
      (node (ref "R45") (pin "1") (pinfunction "A_1") (pintype "passive"))
      (node (ref "R46") (pin "1") (pinfunction "A_1") (pintype "passive"))
      (node (ref "R51") (pin "1") (pinfunction "1_1") (pintype "passive"))
      (node (ref "R52") (pin "1") (pinfunction "1_1") (pintype "passive"))
      (node (ref "R53") (pin "1") (pinfunction "1_1") (pintype "passive"))
      (node (ref "R54") (pin "1") (pinfunction "1_1") (pintype "passive"))
      (node (ref "R55") (pin "1") (pinfunction "1_1") (pintype "passive"))
      (node (ref "R57") (pin "2") (pinfunction "2_2") (pintype "passive"))
      (node (ref "R58") (pin "1") (pinfunction "1_1") (pintype "passive"))
      (node (ref "R72") (pin "1") (pinfunction "A_1") (pintype "passive"))
      (node (ref "R73") (pin "1") (pinfunction "A_1") (pintype "passive"))
      (node (ref "R78") (pin "1") (pinfunction "1_1") (pintype "passive"))
      (node (ref "R79") (pin "1") (pinfunction "1_1") (pintype "passive"))
      (node (ref "R80") (pin "1") (pinfunction "1_1") (pintype "passive"))
      (node (ref "R81") (pin "1") (pinfunction "1_1") (pintype "passive"))
      (node (ref "R82") (pin "1") (pinfunction "1_1") (pintype "passive"))
      (node (ref "R84") (pin "2") (pinfunction "2_2") (pintype "passive"))
      (node (ref "R85") (pin "1") (pinfunction "1_1") (pintype "passive"))
      (node (ref "SA11") (pin "P$3") (pinfunction "2_P$3") (pintype "passive"))
      (node (ref "SA11") (pin "P$4") (pinfunction "2_P$4") (pintype "passive"))
      (node (ref "SA14") (pin "1$S") (pinfunction "S_1$S") (pintype "passive"))
      (node (ref "SA16") (pin "P$3") (pinfunction "2_P$3") (pintype "passive"))
      (node (ref "SA16") (pin "P$4") (pinfunction "2_P$4") (pintype "passive"))
      (node (ref "SA4") (pin "1$S") (pinfunction "S_1$S") (pintype "passive"))
      (node (ref "SA6") (pin "P$3") (pinfunction "2_P$3") (pintype "passive"))
      (node (ref "SA6") (pin "P$4") (pinfunction "2_P$4") (pintype "passive"))
      (node (ref "SA9") (pin "1$S") (pinfunction "S_1$S") (pintype "passive"))
      (node (ref "VT10") (pin "3") (pinfunction "E_3") (pintype "passive"))
      (node (ref "VT11") (pin "3") (pinfunction "E_3") (pintype "passive"))
      (node (ref "VT12") (pin "3") (pinfunction "E_3") (pintype "passive"))
      (node (ref "VT17") (pin "3") (pinfunction "E_3") (pintype "passive"))
      (node (ref "VT18") (pin "3") (pinfunction "E_3") (pintype "passive"))
      (node (ref "VT19") (pin "3") (pinfunction "E_3") (pintype "passive"))
      (node (ref "VT3") (pin "3") (pinfunction "E_3") (pintype "passive"))
      (node (ref "VT4") (pin "3") (pinfunction "E_3") (pintype "passive"))
      (node (ref "VT5") (pin "3") (pinfunction "E_3") (pintype "passive"))
      (node (ref "XS7") (pin "P$2") (pinfunction "2_P$2") (pintype "passive"))
    )
    (net (code "28") (name "Net-(C5-Pad1)") (class "Default")
      (node (ref "C5") (pin "1") (pinfunction "1_1") (pintype "passive"))
      (node (ref "R17") (pin "2") (pinfunction "2_2") (pintype "passive"))
      (node (ref "R87") (pin "2") (pinfunction "2_2") (pintype "passive"))
      (node (ref "SA6") (pin "P$1") (pinfunction "1_P$1") (pintype "passive"))
      (node (ref "SA6") (pin "P$2") (pinfunction "1_P$2") (pintype "passive"))
    )
    (net (code "29") (name "Net-(C9-Pad1)") (class "Default")
      (node (ref "C9") (pin "1") (pinfunction "1_1") (pintype "passive"))
      (node (ref "R47") (pin "2") (pinfunction "2_2") (pintype "passive"))
      (node (ref "R88") (pin "2") (pinfunction "2_2") (pintype "passive"))
      (node (ref "SA11") (pin "P$1") (pinfunction "1_P$1") (pintype "passive"))
      (node (ref "SA11") (pin "P$2") (pinfunction "1_P$2") (pintype "passive"))
    )
    (net (code "30") (name "Net-(C13-Pad1)") (class "Default")
      (node (ref "C13") (pin "1") (pinfunction "1_1") (pintype "passive"))
      (node (ref "R74") (pin "2") (pinfunction "2_2") (pintype "passive"))
      (node (ref "R89") (pin "2") (pinfunction "2_2") (pintype "passive"))
      (node (ref "SA16") (pin "P$1") (pinfunction "1_P$1") (pintype "passive"))
      (node (ref "SA16") (pin "P$2") (pinfunction "1_P$2") (pintype "passive"))
    )
    (net (code "31") (name "Net-(D1-ANODE)") (class "Default")
      (node (ref "D1") (pin "A") (pinfunction "ANODE_A") (pintype "passive"))
      (node (ref "R5") (pin "1") (pinfunction "1_1") (pintype "passive"))
      (node (ref "R6") (pin "1") (pinfunction "1_1") (pintype "passive"))
      (node (ref "VT3") (pin "2") (pinfunction "B_2") (pintype "passive"))
      (node (ref "VT4") (pin "1") (pinfunction "C_1") (pintype "passive"))
    )
    (net (code "32") (name "Net-(D2-ANODE)") (class "Default")
      (node (ref "D2") (pin "A") (pinfunction "ANODE_A") (pintype "passive"))
      (node (ref "D3") (pin "A") (pinfunction "ANODE_A") (pintype "passive"))
      (node (ref "R7") (pin "1") (pinfunction "1_1") (pintype "passive"))
      (node (ref "VT5") (pin "2") (pinfunction "B_2") (pintype "passive"))
    )
    (net (code "33") (name "Net-(D4-ANODE)") (class "Default")
      (node (ref "C3") (pin "+") (pinfunction "+_+") (pintype "passive"))
      (node (ref "D4") (pin "A") (pinfunction "ANODE_A") (pintype "passive"))
      (node (ref "DA2") (pin "2") (pinfunction "VO_2") (pintype "passive"))
      (node (ref "R11") (pin "2") (pinfunction "2_2") (pintype "passive"))
    )
    (net (code "34") (name "Net-(D4-CATHODE)") (class "Default")
      (node (ref "D4") (pin "C") (pinfunction "CATHODE_C") (pintype "passive"))
      (node (ref "R10") (pin "1") (pinfunction "1_1") (pintype "passive"))
      (node (ref "R10") (pin "3") (pinfunction "1_3") (pintype "passive"))
      (node (ref "VT6") (pin "3") (pinfunction "D_3") (pintype "passive"))
    )
    (net (code "35") (name "Net-(D5-ANODE)") (class "Default")
      (node (ref "C4") (pin "+") (pinfunction "+_+") (pintype "passive"))
      (node (ref "D5") (pin "A") (pinfunction "ANODE_A") (pintype "passive"))
      (node (ref "DA3") (pin "2") (pinfunction "VO_2") (pintype "passive"))
      (node (ref "R13") (pin "2") (pinfunction "2_2") (pintype "passive"))
    )
    (net (code "36") (name "Net-(D5-CATHODE)") (class "Default")
      (node (ref "D5") (pin "C") (pinfunction "CATHODE_C") (pintype "passive"))
      (node (ref "VT7") (pin "3") (pinfunction "D_3") (pintype "passive"))
      (node (ref "XS1") (pin "P$1") (pinfunction "1_P$1") (pintype "passive"))
      (node (ref "XS2") (pin "1") (pinfunction "1_1") (pintype "passive"))
    )
    (net (code "37") (name "Net-(D6-ANODE)") (class "Default")
      (node (ref "D6") (pin "A") (pinfunction "ANODE_A") (pintype "passive"))
      (node (ref "R32") (pin "1") (pinfunction "1_1") (pintype "passive"))
      (node (ref "R33") (pin "1") (pinfunction "1_1") (pintype "passive"))
      (node (ref "VT10") (pin "2") (pinfunction "B_2") (pintype "passive"))
      (node (ref "VT11") (pin "1") (pinfunction "C_1") (pintype "passive"))
    )
    (net (code "38") (name "Net-(D7-ANODE)") (class "Default")
      (node (ref "D7") (pin "A") (pinfunction "ANODE_A") (pintype "passive"))
      (node (ref "D8") (pin "A") (pinfunction "ANODE_A") (pintype "passive"))
      (node (ref "R34") (pin "1") (pinfunction "1_1") (pintype "passive"))
      (node (ref "VT12") (pin "2") (pinfunction "B_2") (pintype "passive"))
    )
    (net (code "39") (name "Net-(D9-ANODE)") (class "Default")
      (node (ref "C7") (pin "+") (pinfunction "+_+") (pintype "passive"))
      (node (ref "D9") (pin "A") (pinfunction "ANODE_A") (pintype "passive"))
      (node (ref "DA4") (pin "2") (pinfunction "VO_2") (pintype "passive"))
      (node (ref "R38") (pin "2") (pinfunction "2_2") (pintype "passive"))
    )
    (net (code "40") (name "Net-(D9-CATHODE)") (class "Default")
      (node (ref "D9") (pin "C") (pinfunction "CATHODE_C") (pintype "passive"))
      (node (ref "R37") (pin "1") (pinfunction "1_1") (pintype "passive"))
      (node (ref "R37") (pin "3") (pinfunction "1_3") (pintype "passive"))
      (node (ref "VT13") (pin "3") (pinfunction "D_3") (pintype "passive"))
    )
    (net (code "41") (name "Net-(D10-ANODE)") (class "Default")
      (node (ref "C8") (pin "+") (pinfunction "+_+") (pintype "passive"))
      (node (ref "D10") (pin "A") (pinfunction "ANODE_A") (pintype "passive"))
      (node (ref "DA5") (pin "2") (pinfunction "VO_2") (pintype "passive"))
      (node (ref "R40") (pin "2") (pinfunction "2_2") (pintype "passive"))
    )
    (net (code "42") (name "Net-(D10-CATHODE)") (class "Default")
      (node (ref "D10") (pin "C") (pinfunction "CATHODE_C") (pintype "passive"))
      (node (ref "VT14") (pin "3") (pinfunction "D_3") (pintype "passive"))
      (node (ref "XS3") (pin "P$1") (pinfunction "1_P$1") (pintype "passive"))
      (node (ref "XS4") (pin "1") (pinfunction "1_1") (pintype "passive"))
    )
    (net (code "43") (name "Net-(D11-ANODE)") (class "Default")
      (node (ref "D11") (pin "A") (pinfunction "ANODE_A") (pintype "passive"))
      (node (ref "R62") (pin "1") (pinfunction "1_1") (pintype "passive"))
      (node (ref "R63") (pin "1") (pinfunction "1_1") (pintype "passive"))
      (node (ref "VT17") (pin "2") (pinfunction "B_2") (pintype "passive"))
      (node (ref "VT18") (pin "1") (pinfunction "C_1") (pintype "passive"))
    )
    (net (code "44") (name "Net-(D12-ANODE)") (class "Default")
      (node (ref "D12") (pin "A") (pinfunction "ANODE_A") (pintype "passive"))
      (node (ref "D13") (pin "A") (pinfunction "ANODE_A") (pintype "passive"))
      (node (ref "R64") (pin "1") (pinfunction "1_1") (pintype "passive"))
      (node (ref "VT19") (pin "2") (pinfunction "B_2") (pintype "passive"))
    )
    (net (code "45") (name "Net-(D14-ANODE)") (class "Default")
      (node (ref "C11") (pin "+") (pinfunction "+_+") (pintype "passive"))
      (node (ref "D14") (pin "A") (pinfunction "ANODE_A") (pintype "passive"))
      (node (ref "DA6") (pin "2") (pinfunction "VO_2") (pintype "passive"))
      (node (ref "R68") (pin "2") (pinfunction "2_2") (pintype "passive"))
    )
    (net (code "46") (name "Net-(D14-CATHODE)") (class "Default")
      (node (ref "D14") (pin "C") (pinfunction "CATHODE_C") (pintype "passive"))
      (node (ref "R67") (pin "1") (pinfunction "1_1") (pintype "passive"))
      (node (ref "R67") (pin "3") (pinfunction "1_3") (pintype "passive"))
      (node (ref "VT20") (pin "3") (pinfunction "D_3") (pintype "passive"))
    )
    (net (code "47") (name "Net-(D15-ANODE)") (class "Default")
      (node (ref "C12") (pin "+") (pinfunction "+_+") (pintype "passive"))
      (node (ref "D15") (pin "A") (pinfunction "ANODE_A") (pintype "passive"))
      (node (ref "DA7") (pin "2") (pinfunction "VO_2") (pintype "passive"))
      (node (ref "R70") (pin "2") (pinfunction "2_2") (pintype "passive"))
    )
    (net (code "48") (name "Net-(D15-CATHODE)") (class "Default")
      (node (ref "D15") (pin "C") (pinfunction "CATHODE_C") (pintype "passive"))
      (node (ref "VT21") (pin "3") (pinfunction "D_3") (pintype "passive"))
      (node (ref "XS5") (pin "P$1") (pinfunction "1_P$1") (pintype "passive"))
      (node (ref "XS6") (pin "1") (pinfunction "1_1") (pintype "passive"))
    )
    (net (code "49") (name "Net-(DA1-ADJ)") (class "Default")
      (node (ref "DA1") (pin "1") (pinfunction "ADJ_1") (pintype "passive"))
      (node (ref "R1") (pin "1") (pinfunction "1_1") (pintype "passive"))
      (node (ref "R2") (pin "2") (pinfunction "2_2") (pintype "passive"))
    )
    (net (code "50") (name "Net-(DA2-ADJ)") (class "Default")
      (node (ref "DA2") (pin "1") (pinfunction "ADJ_1") (pintype "passive"))
      (node (ref "R15") (pin "2") (pinfunction "S_2") (pintype "passive"))
    )
    (net (code "51") (name "Net-(DA2-VI)") (class "Default")
      (node (ref "DA2") (pin "3") (pinfunction "VI_3") (pintype "input"))
      (node (ref "R12") (pin "2") (pinfunction "2_2") (pintype "passive"))
      (node (ref "R20") (pin "1") (pinfunction "1_1") (pintype "passive"))
      (node (ref "VT1") (pin "3") (pinfunction "D_3") (pintype "passive"))
    )
    (net (code "52") (name "Net-(DA3-ADJ)") (class "Default")
      (node (ref "DA3") (pin "1") (pinfunction "ADJ_1") (pintype "passive"))
      (node (ref "R16") (pin "2") (pinfunction "S_2") (pintype "passive"))
    )
    (net (code "53") (name "Net-(DA3-VI)") (class "Default")
      (node (ref "DA3") (pin "3") (pinfunction "VI_3") (pintype "input"))
      (node (ref "R14") (pin "2") (pinfunction "2_2") (pintype "passive"))
      (node (ref "R18") (pin "2") (pinfunction "2_2") (pintype "passive"))
      (node (ref "VT2") (pin "3") (pinfunction "D_3") (pintype "passive"))
    )
    (net (code "54") (name "Net-(DA4-ADJ)") (class "Default")
      (node (ref "DA4") (pin "1") (pinfunction "ADJ_1") (pintype "passive"))
      (node (ref "R45") (pin "2") (pinfunction "S_2") (pintype "passive"))
    )
    (net (code "55") (name "Net-(DA4-VI)") (class "Default")
      (node (ref "DA4") (pin "3") (pinfunction "VI_3") (pintype "input"))
      (node (ref "R39") (pin "2") (pinfunction "2_2") (pintype "passive"))
      (node (ref "R50") (pin "1") (pinfunction "1_1") (pintype "passive"))
      (node (ref "VT8") (pin "3") (pinfunction "D_3") (pintype "passive"))
    )
    (net (code "56") (name "Net-(DA5-ADJ)") (class "Default")
      (node (ref "DA5") (pin "1") (pinfunction "ADJ_1") (pintype "passive"))
      (node (ref "R46") (pin "2") (pinfunction "S_2") (pintype "passive"))
    )
    (net (code "57") (name "Net-(DA5-VI)") (class "Default")
      (node (ref "DA5") (pin "3") (pinfunction "VI_3") (pintype "input"))
      (node (ref "R41") (pin "2") (pinfunction "2_2") (pintype "passive"))
      (node (ref "R48") (pin "2") (pinfunction "2_2") (pintype "passive"))
      (node (ref "VT9") (pin "3") (pinfunction "D_3") (pintype "passive"))
    )
    (net (code "58") (name "Net-(DA6-ADJ)") (class "Default")
      (node (ref "DA6") (pin "1") (pinfunction "ADJ_1") (pintype "passive"))
      (node (ref "R72") (pin "2") (pinfunction "S_2") (pintype "passive"))
    )
    (net (code "59") (name "Net-(DA6-VI)") (class "Default")
      (node (ref "DA6") (pin "3") (pinfunction "VI_3") (pintype "input"))
      (node (ref "R69") (pin "2") (pinfunction "2_2") (pintype "passive"))
      (node (ref "R77") (pin "1") (pinfunction "1_1") (pintype "passive"))
      (node (ref "VT15") (pin "3") (pinfunction "D_3") (pintype "passive"))
    )
    (net (code "60") (name "Net-(DA7-ADJ)") (class "Default")
      (node (ref "DA7") (pin "1") (pinfunction "ADJ_1") (pintype "passive"))
      (node (ref "R73") (pin "2") (pinfunction "S_2") (pintype "passive"))
    )
    (net (code "61") (name "Net-(DA7-VI)") (class "Default")
      (node (ref "DA7") (pin "3") (pinfunction "VI_3") (pintype "input"))
      (node (ref "R71") (pin "2") (pinfunction "2_2") (pintype "passive"))
      (node (ref "R75") (pin "2") (pinfunction "2_2") (pintype "passive"))
      (node (ref "VT16") (pin "3") (pinfunction "D_3") (pintype "passive"))
    )
    (net (code "62") (name "Net-(DD1-PA8)") (class "Default")
      (node (ref "DD1") (pin "P$5") (pinfunction "PA8_P$5") (pintype "bidirectional"))
      (node (ref "JP1") (pin "3") (pinfunction "3_3") (pintype "passive"))
    )
    (net (code "63") (name "Net-(DD1-PA9)") (class "Default")
      (node (ref "DD1") (pin "P$6") (pinfunction "PA9_P$6") (pintype "bidirectional"))
      (node (ref "JP1") (pin "2") (pinfunction "2_2") (pintype "passive"))
    )
    (net (code "64") (name "Net-(DD1-PA10)") (class "Default")
      (node (ref "DD1") (pin "P$7") (pinfunction "PA10_P$7") (pintype "bidirectional"))
      (node (ref "JP1") (pin "1") (pinfunction "1_1") (pintype "passive"))
    )
    (net (code "65") (name "Net-(DD1-PB5)") (class "Default")
      (node (ref "DD1") (pin "P$13") (pinfunction "PB5_P$13") (pintype "bidirectional"))
      (node (ref "HG1") (pin "P$12") (pinfunction "CS_P$12") (pintype "bidirectional"))
    )
    (net (code "66") (name "Net-(DD1-PB6)") (class "Default")
      (node (ref "DD1") (pin "P$14") (pinfunction "PB6_P$14") (pintype "bidirectional"))
      (node (ref "HG1") (pin "P$11") (pinfunction "RST_P$11") (pintype "bidirectional"))
    )
    (net (code "67") (name "Net-(DD1-PB7)") (class "Default")
      (node (ref "DD1") (pin "P$15") (pinfunction "PB7_P$15") (pintype "bidirectional"))
      (node (ref "HG1") (pin "P$10") (pinfunction "RS_P$10") (pintype "bidirectional"))
    )
    (net (code "68") (name "Net-(DD1-PB8)") (class "Default")
      (node (ref "DD1") (pin "P$16") (pinfunction "PB8_P$16") (pintype "bidirectional"))
      (node (ref "HG1") (pin "P$9") (pinfunction "SDA_P$9") (pintype "bidirectional"))
    )
    (net (code "69") (name "Net-(DD1-PB9)") (class "Default")
      (node (ref "DD1") (pin "P$17") (pinfunction "PB9_P$17") (pintype "bidirectional"))
      (node (ref "HG1") (pin "P$8") (pinfunction "SCK_P$8") (pintype "bidirectional"))
    )
    (net (code "70") (name "Net-(F1-Pad1)") (class "Default")
      (node (ref "F1") (pin "1") (pinfunction "1_1") (pintype "passive"))
      (node (ref "J1") (pin "1") (pinfunction "1_1") (pintype "passive"))
    )
    (net (code "71") (name "Net-(IC1A-+IN)") (class "Default")
      (node (ref "IC1") (pin "3") (pinfunction "+IN_3") (pintype "input"))
      (node (ref "R25") (pin "2") (pinfunction "2_2") (pintype "passive"))
      (node (ref "VT7") (pin "2") (pinfunction "S_2") (pintype "passive"))
    )
    (net (code "72") (name "Net-(IC1A--IN)") (class "Default")
      (node (ref "IC1") (pin "2") (pinfunction "-IN_2") (pintype "input"))
      (node (ref "R28") (pin "2") (pinfunction "2_2") (pintype "passive"))
      (node (ref "R29") (pin "1") (pinfunction "1_1") (pintype "passive"))
    )
    (net (code "73") (name "Net-(IC1B-+IN)") (class "Default")
      (node (ref "IC1") (pin "5") (pinfunction "+IN_5") (pintype "input"))
      (node (ref "R24") (pin "2") (pinfunction "2_2") (pintype "passive"))
      (node (ref "VT6") (pin "2") (pinfunction "S_2") (pintype "passive"))
    )
    (net (code "74") (name "Net-(IC1B--IN)") (class "Default")
      (node (ref "IC1") (pin "6") (pinfunction "-IN_6") (pintype "input"))
      (node (ref "R26") (pin "2") (pinfunction "2_2") (pintype "passive"))
      (node (ref "R27") (pin "1") (pinfunction "1_1") (pintype "passive"))
    )
    (net (code "75") (name "Net-(IC2A-+IN)") (class "Default")
      (node (ref "IC2") (pin "3") (pinfunction "+IN_3") (pintype "input"))
      (node (ref "R55") (pin "2") (pinfunction "2_2") (pintype "passive"))
      (node (ref "VT14") (pin "2") (pinfunction "S_2") (pintype "passive"))
    )
    (net (code "76") (name "Net-(IC2A--IN)") (class "Default")
      (node (ref "IC2") (pin "2") (pinfunction "-IN_2") (pintype "input"))
      (node (ref "R58") (pin "2") (pinfunction "2_2") (pintype "passive"))
      (node (ref "R59") (pin "1") (pinfunction "1_1") (pintype "passive"))
    )
    (net (code "77") (name "Net-(IC2B-+IN)") (class "Default")
      (node (ref "IC2") (pin "5") (pinfunction "+IN_5") (pintype "input"))
      (node (ref "R54") (pin "2") (pinfunction "2_2") (pintype "passive"))
      (node (ref "VT13") (pin "2") (pinfunction "S_2") (pintype "passive"))
    )
    (net (code "78") (name "Net-(IC2B--IN)") (class "Default")
      (node (ref "IC2") (pin "6") (pinfunction "-IN_6") (pintype "input"))
      (node (ref "R56") (pin "2") (pinfunction "2_2") (pintype "passive"))
      (node (ref "R57") (pin "1") (pinfunction "1_1") (pintype "passive"))
    )
    (net (code "79") (name "Net-(IC3A-+IN)") (class "Default")
      (node (ref "IC3") (pin "3") (pinfunction "+IN_3") (pintype "input"))
      (node (ref "R82") (pin "2") (pinfunction "2_2") (pintype "passive"))
      (node (ref "VT21") (pin "2") (pinfunction "S_2") (pintype "passive"))
    )
    (net (code "80") (name "Net-(IC3A--IN)") (class "Default")
      (node (ref "IC3") (pin "2") (pinfunction "-IN_2") (pintype "input"))
      (node (ref "R85") (pin "2") (pinfunction "2_2") (pintype "passive"))
      (node (ref "R86") (pin "1") (pinfunction "1_1") (pintype "passive"))
    )
    (net (code "81") (name "Net-(IC3B-+IN)") (class "Default")
      (node (ref "IC3") (pin "5") (pinfunction "+IN_5") (pintype "input"))
      (node (ref "R81") (pin "2") (pinfunction "2_2") (pintype "passive"))
      (node (ref "VT20") (pin "2") (pinfunction "S_2") (pintype "passive"))
    )
    (net (code "82") (name "Net-(IC3B--IN)") (class "Default")
      (node (ref "IC3") (pin "6") (pinfunction "-IN_6") (pintype "input"))
      (node (ref "R83") (pin "2") (pinfunction "2_2") (pintype "passive"))
      (node (ref "R84") (pin "1") (pinfunction "1_1") (pintype "passive"))
    )
    (net (code "83") (name "Net-(LED1-PadA)") (class "Default")
      (node (ref "LED1") (pin "A") (pinfunction "A_A") (pintype "passive"))
      (node (ref "R12") (pin "1") (pinfunction "1_1") (pintype "passive"))
    )
    (net (code "84") (name "Net-(LED2-PadA)") (class "Default")
      (node (ref "LED2") (pin "A") (pinfunction "A_A") (pintype "passive"))
      (node (ref "R14") (pin "1") (pinfunction "1_1") (pintype "passive"))
    )
    (net (code "85") (name "Net-(LED3-PadA)") (class "Default")
      (node (ref "LED3") (pin "A") (pinfunction "A_A") (pintype "passive"))
      (node (ref "R39") (pin "1") (pinfunction "1_1") (pintype "passive"))
    )
    (net (code "86") (name "Net-(LED4-PadA)") (class "Default")
      (node (ref "LED4") (pin "A") (pinfunction "A_A") (pintype "passive"))
      (node (ref "R41") (pin "1") (pinfunction "1_1") (pintype "passive"))
    )
    (net (code "87") (name "Net-(LED5-PadA)") (class "Default")
      (node (ref "LED5") (pin "A") (pinfunction "A_A") (pintype "passive"))
      (node (ref "R69") (pin "1") (pinfunction "1_1") (pintype "passive"))
    )
    (net (code "88") (name "Net-(LED6-PadA)") (class "Default")
      (node (ref "LED6") (pin "A") (pinfunction "A_A") (pintype "passive"))
      (node (ref "R71") (pin "1") (pinfunction "1_1") (pintype "passive"))
    )
    (net (code "89") (name "Net-(R10B-2)") (class "Default")
      (node (ref "R10") (pin "4") (pinfunction "2_4") (pintype "passive"))
      (node (ref "SA5") (pin "1$P") (pinfunction "P_1$P") (pintype "passive"))
    )
    (net (code "90") (name "Net-(R15-E)") (class "Default")
      (node (ref "R11") (pin "1") (pinfunction "1_1") (pintype "passive"))
      (node (ref "R15") (pin "3") (pinfunction "E_3") (pintype "passive"))
    )
    (net (code "91") (name "Net-(R16-E)") (class "Default")
      (node (ref "R13") (pin "1") (pinfunction "1_1") (pintype "passive"))
      (node (ref "R16") (pin "3") (pinfunction "E_3") (pintype "passive"))
    )
    (net (code "92") (name "Net-(R19-Pad1)") (class "Default")
      (node (ref "R19") (pin "1") (pinfunction "1_1") (pintype "passive"))
      (node (ref "R21") (pin "2") (pinfunction "2_2") (pintype "passive"))
    )
    (net (code "93") (name "Net-(R37B-2)") (class "Default")
      (node (ref "R37") (pin "4") (pinfunction "2_4") (pintype "passive"))
      (node (ref "SA10") (pin "1$P") (pinfunction "P_1$P") (pintype "passive"))
    )
    (net (code "94") (name "Net-(R45-E)") (class "Default")
      (node (ref "R38") (pin "1") (pinfunction "1_1") (pintype "passive"))
      (node (ref "R45") (pin "3") (pinfunction "E_3") (pintype "passive"))
    )
    (net (code "95") (name "Net-(R46-E)") (class "Default")
      (node (ref "R40") (pin "1") (pinfunction "1_1") (pintype "passive"))
      (node (ref "R46") (pin "3") (pinfunction "E_3") (pintype "passive"))
    )
    (net (code "96") (name "Net-(R49-Pad1)") (class "Default")
      (node (ref "R49") (pin "1") (pinfunction "1_1") (pintype "passive"))
      (node (ref "R51") (pin "2") (pinfunction "2_2") (pintype "passive"))
    )
    (net (code "97") (name "Net-(R67B-2)") (class "Default")
      (node (ref "R67") (pin "4") (pinfunction "2_4") (pintype "passive"))
      (node (ref "SA15") (pin "1$P") (pinfunction "P_1$P") (pintype "passive"))
    )
    (net (code "98") (name "Net-(R72-E)") (class "Default")
      (node (ref "R68") (pin "1") (pinfunction "1_1") (pintype "passive"))
      (node (ref "R72") (pin "3") (pinfunction "E_3") (pintype "passive"))
    )
    (net (code "99") (name "Net-(R73-E)") (class "Default")
      (node (ref "R70") (pin "1") (pinfunction "1_1") (pintype "passive"))
      (node (ref "R73") (pin "3") (pinfunction "E_3") (pintype "passive"))
    )
    (net (code "100") (name "Net-(R76-Pad1)") (class "Default")
      (node (ref "R76") (pin "1") (pinfunction "1_1") (pintype "passive"))
      (node (ref "R78") (pin "2") (pinfunction "2_2") (pintype "passive"))
    )
    (net (code "101") (name "Net-(SA1-P)") (class "Default")
      (node (ref "F1") (pin "2") (pinfunction "2_2") (pintype "passive"))
      (node (ref "SA1") (pin "3") (pinfunction "P_3") (pintype "passive"))
    )
    (net (code "102") (name "Net-(SA2-S)") (class "Default")
      (node (ref "C6") (pin "1") (pinfunction "1_1") (pintype "passive"))
      (node (ref "SA2") (pin "1$S") (pinfunction "S_1$S") (pintype "passive"))
      (node (ref "SA4") (pin "1$P") (pinfunction "P_1$P") (pintype "passive"))
    )
    (net (code "103") (name "Net-(SA3-P)") (class "Default")
      (node (ref "R10") (pin "2") (pinfunction "2_2") (pintype "passive"))
      (node (ref "SA3") (pin "1$P") (pinfunction "P_1$P") (pintype "passive"))
    )
    (net (code "104") (name "Net-(SA3-S)") (class "Default")
      (node (ref "SA3") (pin "1$S") (pinfunction "S_1$S") (pintype "passive"))
      (node (ref "SA5") (pin "1$S") (pinfunction "S_1$S") (pintype "passive"))
      (node (ref "XS1") (pin "P$2") (pinfunction "2_P$2") (pintype "passive"))
      (node (ref "XS2") (pin "2") (pinfunction "2_2") (pintype "passive"))
    )
    (net (code "105") (name "Net-(SA4-O)") (class "Default")
      (node (ref "R8") (pin "1") (pinfunction "1_1") (pintype "passive"))
      (node (ref "SA4") (pin "1$O") (pinfunction "O_1$O") (pintype "passive"))
    )
    (net (code "106") (name "Net-(SA7-S)") (class "Default")
      (node (ref "C10") (pin "1") (pinfunction "1_1") (pintype "passive"))
      (node (ref "SA7") (pin "1$S") (pinfunction "S_1$S") (pintype "passive"))
      (node (ref "SA9") (pin "1$P") (pinfunction "P_1$P") (pintype "passive"))
    )
    (net (code "107") (name "Net-(SA8-P)") (class "Default")
      (node (ref "R37") (pin "2") (pinfunction "2_2") (pintype "passive"))
      (node (ref "SA8") (pin "1$P") (pinfunction "P_1$P") (pintype "passive"))
    )
    (net (code "108") (name "Net-(SA9-O)") (class "Default")
      (node (ref "R35") (pin "1") (pinfunction "1_1") (pintype "passive"))
      (node (ref "SA9") (pin "1$O") (pinfunction "O_1$O") (pintype "passive"))
    )
    (net (code "109") (name "Net-(SA10-S)") (class "Default")
      (node (ref "SA10") (pin "1$S") (pinfunction "S_1$S") (pintype "passive"))
      (node (ref "SA8") (pin "1$S") (pinfunction "S_1$S") (pintype "passive"))
      (node (ref "XS3") (pin "P$2") (pinfunction "2_P$2") (pintype "passive"))
      (node (ref "XS4") (pin "2") (pinfunction "2_2") (pintype "passive"))
    )
    (net (code "110") (name "Net-(SA12-S)") (class "Default")
      (node (ref "C14") (pin "1") (pinfunction "1_1") (pintype "passive"))
      (node (ref "SA12") (pin "1$S") (pinfunction "S_1$S") (pintype "passive"))
      (node (ref "SA14") (pin "1$P") (pinfunction "P_1$P") (pintype "passive"))
    )
    (net (code "111") (name "Net-(SA13-P)") (class "Default")
      (node (ref "R67") (pin "2") (pinfunction "2_2") (pintype "passive"))
      (node (ref "SA13") (pin "1$P") (pinfunction "P_1$P") (pintype "passive"))
    )
    (net (code "112") (name "Net-(SA13-S)") (class "Default")
      (node (ref "SA13") (pin "1$S") (pinfunction "S_1$S") (pintype "passive"))
      (node (ref "SA15") (pin "1$S") (pinfunction "S_1$S") (pintype "passive"))
      (node (ref "XS5") (pin "P$2") (pinfunction "2_P$2") (pintype "passive"))
      (node (ref "XS6") (pin "2") (pinfunction "2_2") (pintype "passive"))
    )
    (net (code "113") (name "Net-(SA14-O)") (class "Default")
      (node (ref "R65") (pin "1") (pinfunction "1_1") (pintype "passive"))
      (node (ref "SA14") (pin "1$O") (pinfunction "O_1$O") (pintype "passive"))
    )
    (net (code "114") (name "Net-(VT1-G)") (class "Default")
      (node (ref "R3") (pin "1") (pinfunction "1_1") (pintype "passive"))
      (node (ref "VT1") (pin "1") (pinfunction "G_1") (pintype "passive"))
      (node (ref "VT3") (pin "1") (pinfunction "C_1") (pintype "passive"))
    )
    (net (code "115") (name "Net-(VT2-G)") (class "Default")
      (node (ref "R4") (pin "1") (pinfunction "1_1") (pintype "passive"))
      (node (ref "VT2") (pin "1") (pinfunction "G_1") (pintype "passive"))
      (node (ref "VT5") (pin "1") (pinfunction "C_1") (pintype "passive"))
    )
    (net (code "116") (name "Net-(VT4-B)") (class "Default")
      (node (ref "R9") (pin "1") (pinfunction "1_1") (pintype "passive"))
      (node (ref "VT4") (pin "2") (pinfunction "B_2") (pintype "passive"))
    )
    (net (code "117") (name "Net-(VT6-G)") (class "Default")
      (node (ref "R18") (pin "1") (pinfunction "1_1") (pintype "passive"))
      (node (ref "R22") (pin "2") (pinfunction "2_2") (pintype "passive"))
      (node (ref "VT6") (pin "1") (pinfunction "G_1") (pintype "passive"))
    )
    (net (code "118") (name "Net-(VT7-G)") (class "Default")
      (node (ref "R20") (pin "2") (pinfunction "2_2") (pintype "passive"))
      (node (ref "R23") (pin "2") (pinfunction "2_2") (pintype "passive"))
      (node (ref "VT7") (pin "1") (pinfunction "G_1") (pintype "passive"))
    )
    (net (code "119") (name "Net-(VT10-C)") (class "Default")
      (node (ref "R30") (pin "1") (pinfunction "1_1") (pintype "passive"))
      (node (ref "VT10") (pin "1") (pinfunction "C_1") (pintype "passive"))
      (node (ref "VT8") (pin "1") (pinfunction "G_1") (pintype "passive"))
    )
    (net (code "120") (name "Net-(VT11-B)") (class "Default")
      (node (ref "R36") (pin "1") (pinfunction "1_1") (pintype "passive"))
      (node (ref "VT11") (pin "2") (pinfunction "B_2") (pintype "passive"))
    )
    (net (code "121") (name "Net-(VT12-C)") (class "Default")
      (node (ref "R31") (pin "1") (pinfunction "1_1") (pintype "passive"))
      (node (ref "VT12") (pin "1") (pinfunction "C_1") (pintype "passive"))
      (node (ref "VT9") (pin "1") (pinfunction "G_1") (pintype "passive"))
    )
    (net (code "122") (name "Net-(VT13-G)") (class "Default")
      (node (ref "R48") (pin "1") (pinfunction "1_1") (pintype "passive"))
      (node (ref "R52") (pin "2") (pinfunction "2_2") (pintype "passive"))
      (node (ref "VT13") (pin "1") (pinfunction "G_1") (pintype "passive"))
    )
    (net (code "123") (name "Net-(VT14-G)") (class "Default")
      (node (ref "R50") (pin "2") (pinfunction "2_2") (pintype "passive"))
      (node (ref "R53") (pin "2") (pinfunction "2_2") (pintype "passive"))
      (node (ref "VT14") (pin "1") (pinfunction "G_1") (pintype "passive"))
    )
    (net (code "124") (name "Net-(VT15-G)") (class "Default")
      (node (ref "R60") (pin "1") (pinfunction "1_1") (pintype "passive"))
      (node (ref "VT15") (pin "1") (pinfunction "G_1") (pintype "passive"))
      (node (ref "VT17") (pin "1") (pinfunction "C_1") (pintype "passive"))
    )
    (net (code "125") (name "Net-(VT16-G)") (class "Default")
      (node (ref "R61") (pin "1") (pinfunction "1_1") (pintype "passive"))
      (node (ref "VT16") (pin "1") (pinfunction "G_1") (pintype "passive"))
      (node (ref "VT19") (pin "1") (pinfunction "C_1") (pintype "passive"))
    )
    (net (code "126") (name "Net-(VT18-B)") (class "Default")
      (node (ref "R66") (pin "1") (pinfunction "1_1") (pintype "passive"))
      (node (ref "VT18") (pin "2") (pinfunction "B_2") (pintype "passive"))
    )
    (net (code "127") (name "Net-(VT20-G)") (class "Default")
      (node (ref "R75") (pin "1") (pinfunction "1_1") (pintype "passive"))
      (node (ref "R79") (pin "2") (pinfunction "2_2") (pintype "passive"))
      (node (ref "VT20") (pin "1") (pinfunction "G_1") (pintype "passive"))
    )
    (net (code "128") (name "Net-(VT21-G)") (class "Default")
      (node (ref "R77") (pin "2") (pinfunction "2_2") (pintype "passive"))
      (node (ref "R80") (pin "2") (pinfunction "2_2") (pintype "passive"))
      (node (ref "VT21") (pin "1") (pinfunction "G_1") (pintype "passive"))
    )
    (net (code "129") (name "VCC") (class "Default")
      (node (ref "C2") (pin "+") (pinfunction "+_+") (pintype "passive"))
      (node (ref "DA1") (pin "2") (pinfunction "VO_2") (pintype "passive"))
      (node (ref "DD1") (pin "P$20") (pinfunction "3.3V1_P$20") (pintype "bidirectional"))
      (node (ref "DD1") (pin "P$23") (pinfunction "3.3V_P$23") (pintype "bidirectional"))
      (node (ref "HG1") (pin "P$5") (pinfunction "LED-A_P$5") (pintype "bidirectional"))
      (node (ref "HG1") (pin "P$7") (pinfunction "VCC_P$7") (pintype "bidirectional"))
      (node (ref "R1") (pin "2") (pinfunction "2_2") (pintype "passive"))
      (node (ref "R17") (pin "1") (pinfunction "1_1") (pintype "passive"))
      (node (ref "R19") (pin "3") (pinfunction "2_3") (pintype "passive"))
      (node (ref "R32") (pin "2") (pinfunction "2_2") (pintype "passive"))
      (node (ref "R33") (pin "2") (pinfunction "2_2") (pintype "passive"))
      (node (ref "R34") (pin "2") (pinfunction "2_2") (pintype "passive"))
      (node (ref "R35") (pin "2") (pinfunction "2_2") (pintype "passive"))
      (node (ref "R47") (pin "1") (pinfunction "1_1") (pintype "passive"))
      (node (ref "R49") (pin "3") (pinfunction "2_3") (pintype "passive"))
      (node (ref "R5") (pin "2") (pinfunction "2_2") (pintype "passive"))
      (node (ref "R6") (pin "2") (pinfunction "2_2") (pintype "passive"))
      (node (ref "R62") (pin "2") (pinfunction "2_2") (pintype "passive"))
      (node (ref "R63") (pin "2") (pinfunction "2_2") (pintype "passive"))
      (node (ref "R64") (pin "2") (pinfunction "2_2") (pintype "passive"))
      (node (ref "R65") (pin "2") (pinfunction "2_2") (pintype "passive"))
      (node (ref "R7") (pin "2") (pinfunction "2_2") (pintype "passive"))
      (node (ref "R74") (pin "1") (pinfunction "1_1") (pintype "passive"))
      (node (ref "R76") (pin "3") (pinfunction "2_3") (pintype "passive"))
      (node (ref "R8") (pin "2") (pinfunction "2_2") (pintype "passive"))
      (node (ref "S1") (pin "4") (pinfunction "4_4") (pintype "passive"))
      (node (ref "S1") (pin "5") (pinfunction "5_5") (pintype "passive"))
      (node (ref "S1") (pin "6") (pinfunction "6_6") (pintype "passive"))
    )
    (net (code "130") (name "unconnected-(DD1-5V-PadP$18)") (class "Default")
      (node (ref "DD1") (pin "P$18") (pinfunction "5V_P$18") (pintype "bidirectional"))
    )
    (net (code "131") (name "unconnected-(DD1-PC13-PadP$39)") (class "Default")
      (node (ref "DD1") (pin "P$39") (pinfunction "PC13_P$39") (pintype "bidirectional"))
    )
    (net (code "132") (name "unconnected-(DD1-PC14-PadP$38)") (class "Default")
      (node (ref "DD1") (pin "P$38") (pinfunction "PC14_P$38") (pintype "bidirectional"))
    )
    (net (code "133") (name "unconnected-(DD1-PC15-PadP$37)") (class "Default")
      (node (ref "DD1") (pin "P$37") (pinfunction "PC15_P$37") (pintype "bidirectional"))
    )
    (net (code "134") (name "unconnected-(DD1-RESET-PadP$24)") (class "Default")
      (node (ref "DD1") (pin "P$24") (pinfunction "RESET_P$24") (pintype "bidirectional"))
    )
    (net (code "135") (name "unconnected-(DD1-VBAT-PadP$40)") (class "Default")
      (node (ref "DD1") (pin "P$40") (pinfunction "VBAT_P$40") (pintype "bidirectional"))
    )
    (net (code "136") (name "unconnected-(J1-Pad2)") (class "Default")
      (node (ref "J1") (pin "2") (pinfunction "2_2") (pintype "passive"))
    )
    (net (code "137") (name "unconnected-(SA1-S-Pad2)") (class "Default")
      (node (ref "SA1") (pin "2") (pinfunction "S_2") (pintype "passive"))
    )
    (net (code "138") (name "unconnected-(SA3-O-Pad1$O)") (class "Default")
      (node (ref "SA3") (pin "1$O") (pinfunction "O_1$O") (pintype "passive"))
    )
    (net (code "139") (name "unconnected-(SA5-O-Pad1$O)") (class "Default")
      (node (ref "SA5") (pin "1$O") (pinfunction "O_1$O") (pintype "passive"))
    )
    (net (code "140") (name "unconnected-(SA8-O-Pad1$O)") (class "Default")
      (node (ref "SA8") (pin "1$O") (pinfunction "O_1$O") (pintype "passive"))
    )
    (net (code "141") (name "unconnected-(SA10-O-Pad1$O)") (class "Default")
      (node (ref "SA10") (pin "1$O") (pinfunction "O_1$O") (pintype "passive"))
    )
    (net (code "142") (name "unconnected-(SA13-O-Pad1$O)") (class "Default")
      (node (ref "SA13") (pin "1$O") (pinfunction "O_1$O") (pintype "passive"))
    )
    (net (code "143") (name "unconnected-(SA15-O-Pad1$O)") (class "Default")
      (node (ref "SA15") (pin "1$O") (pinfunction "O_1$O") (pintype "passive"))
    )
  )
)
